# eightbyeight-teardrop.net
KiCad netlist of a schematic drawn in EAGLE
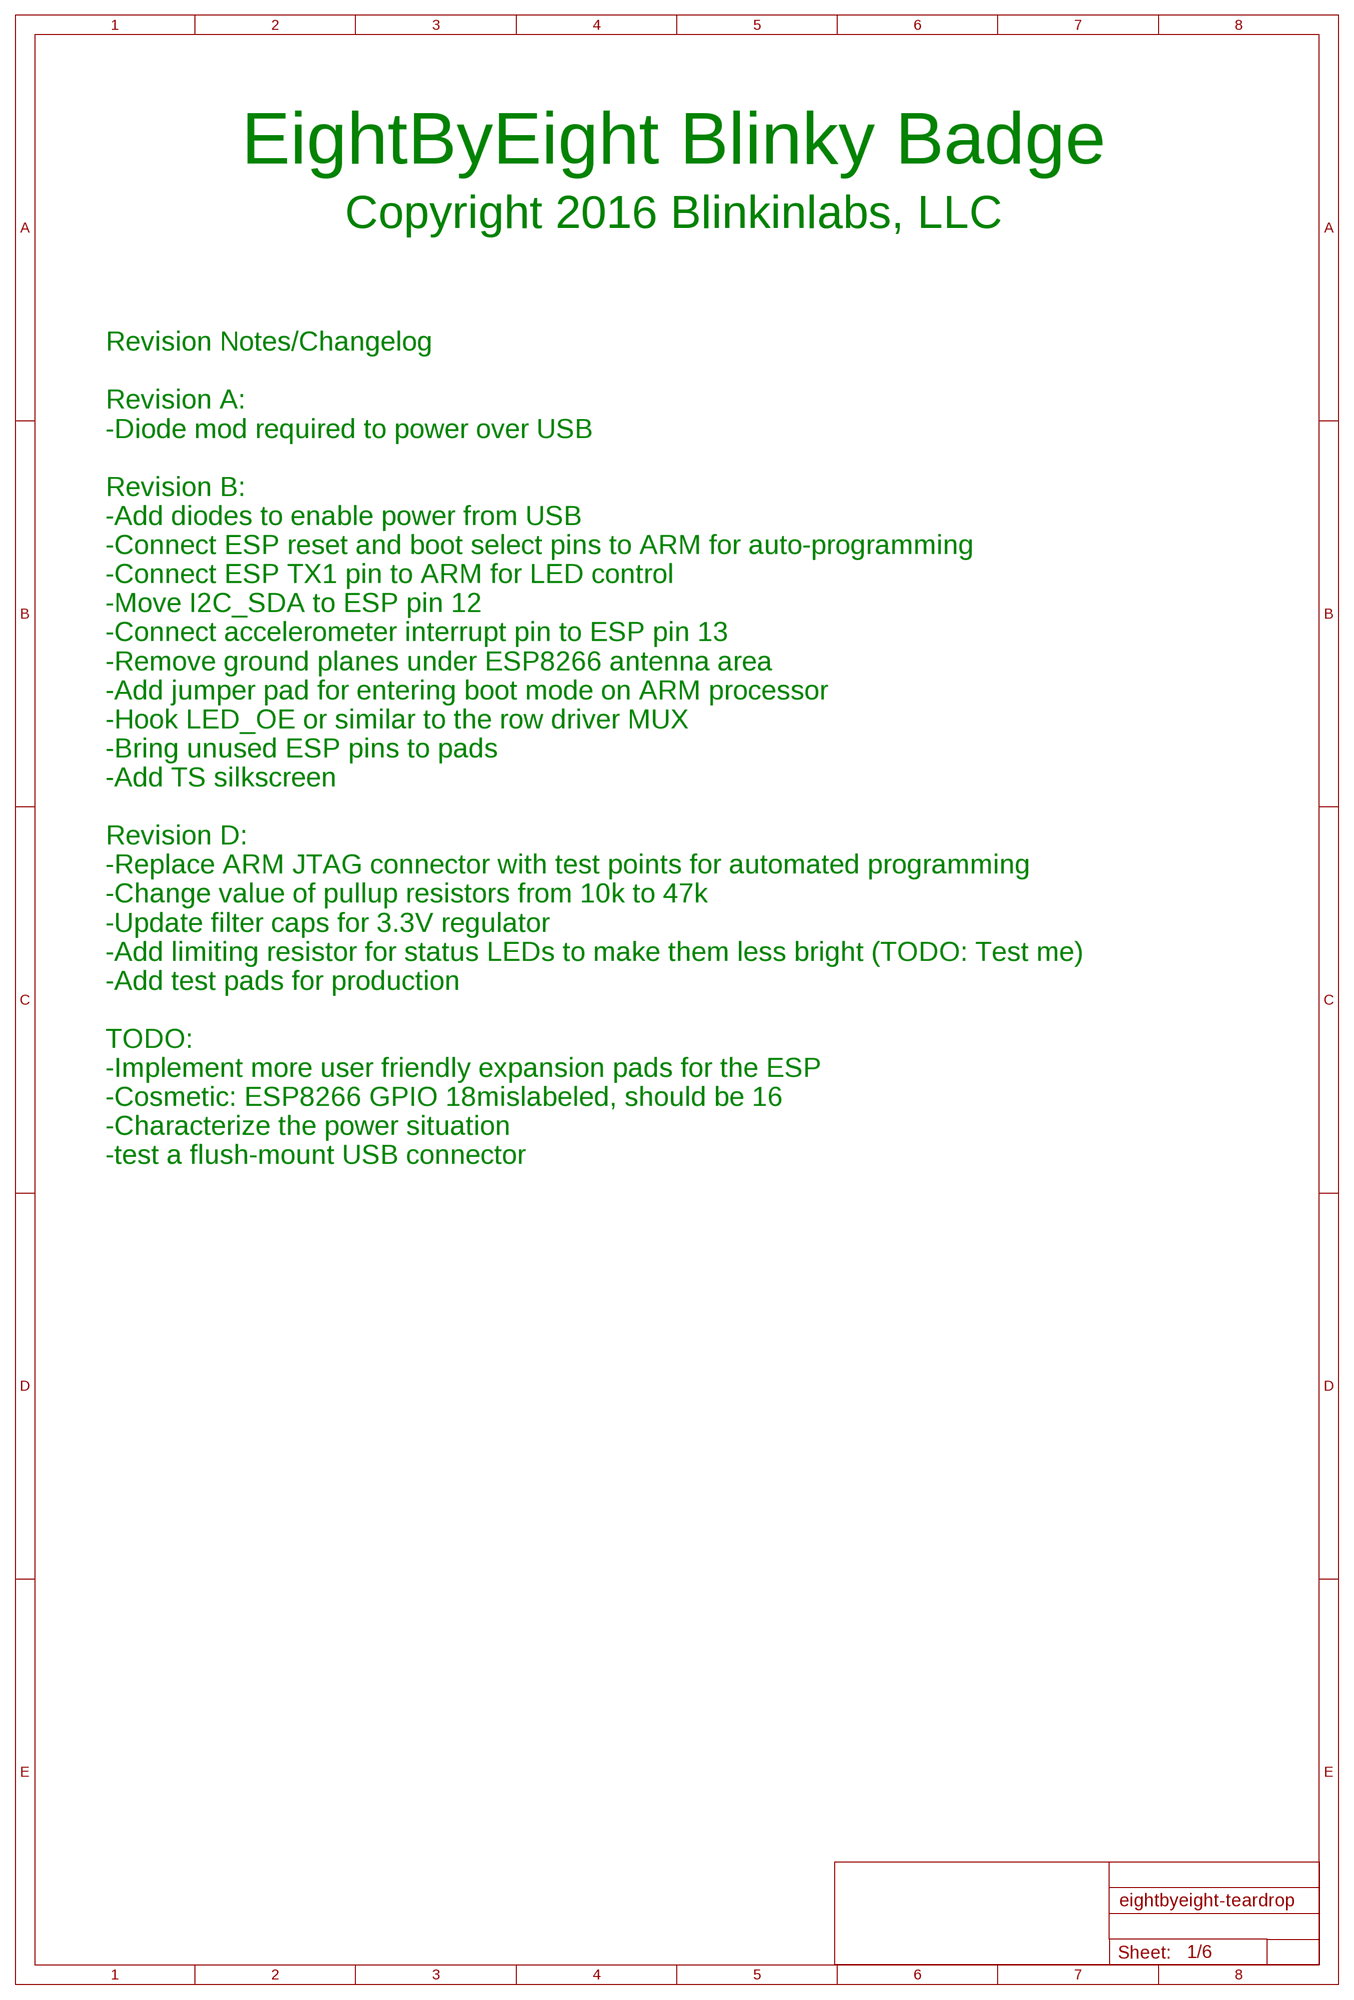
[diagram p0: schematic, sheet 1]
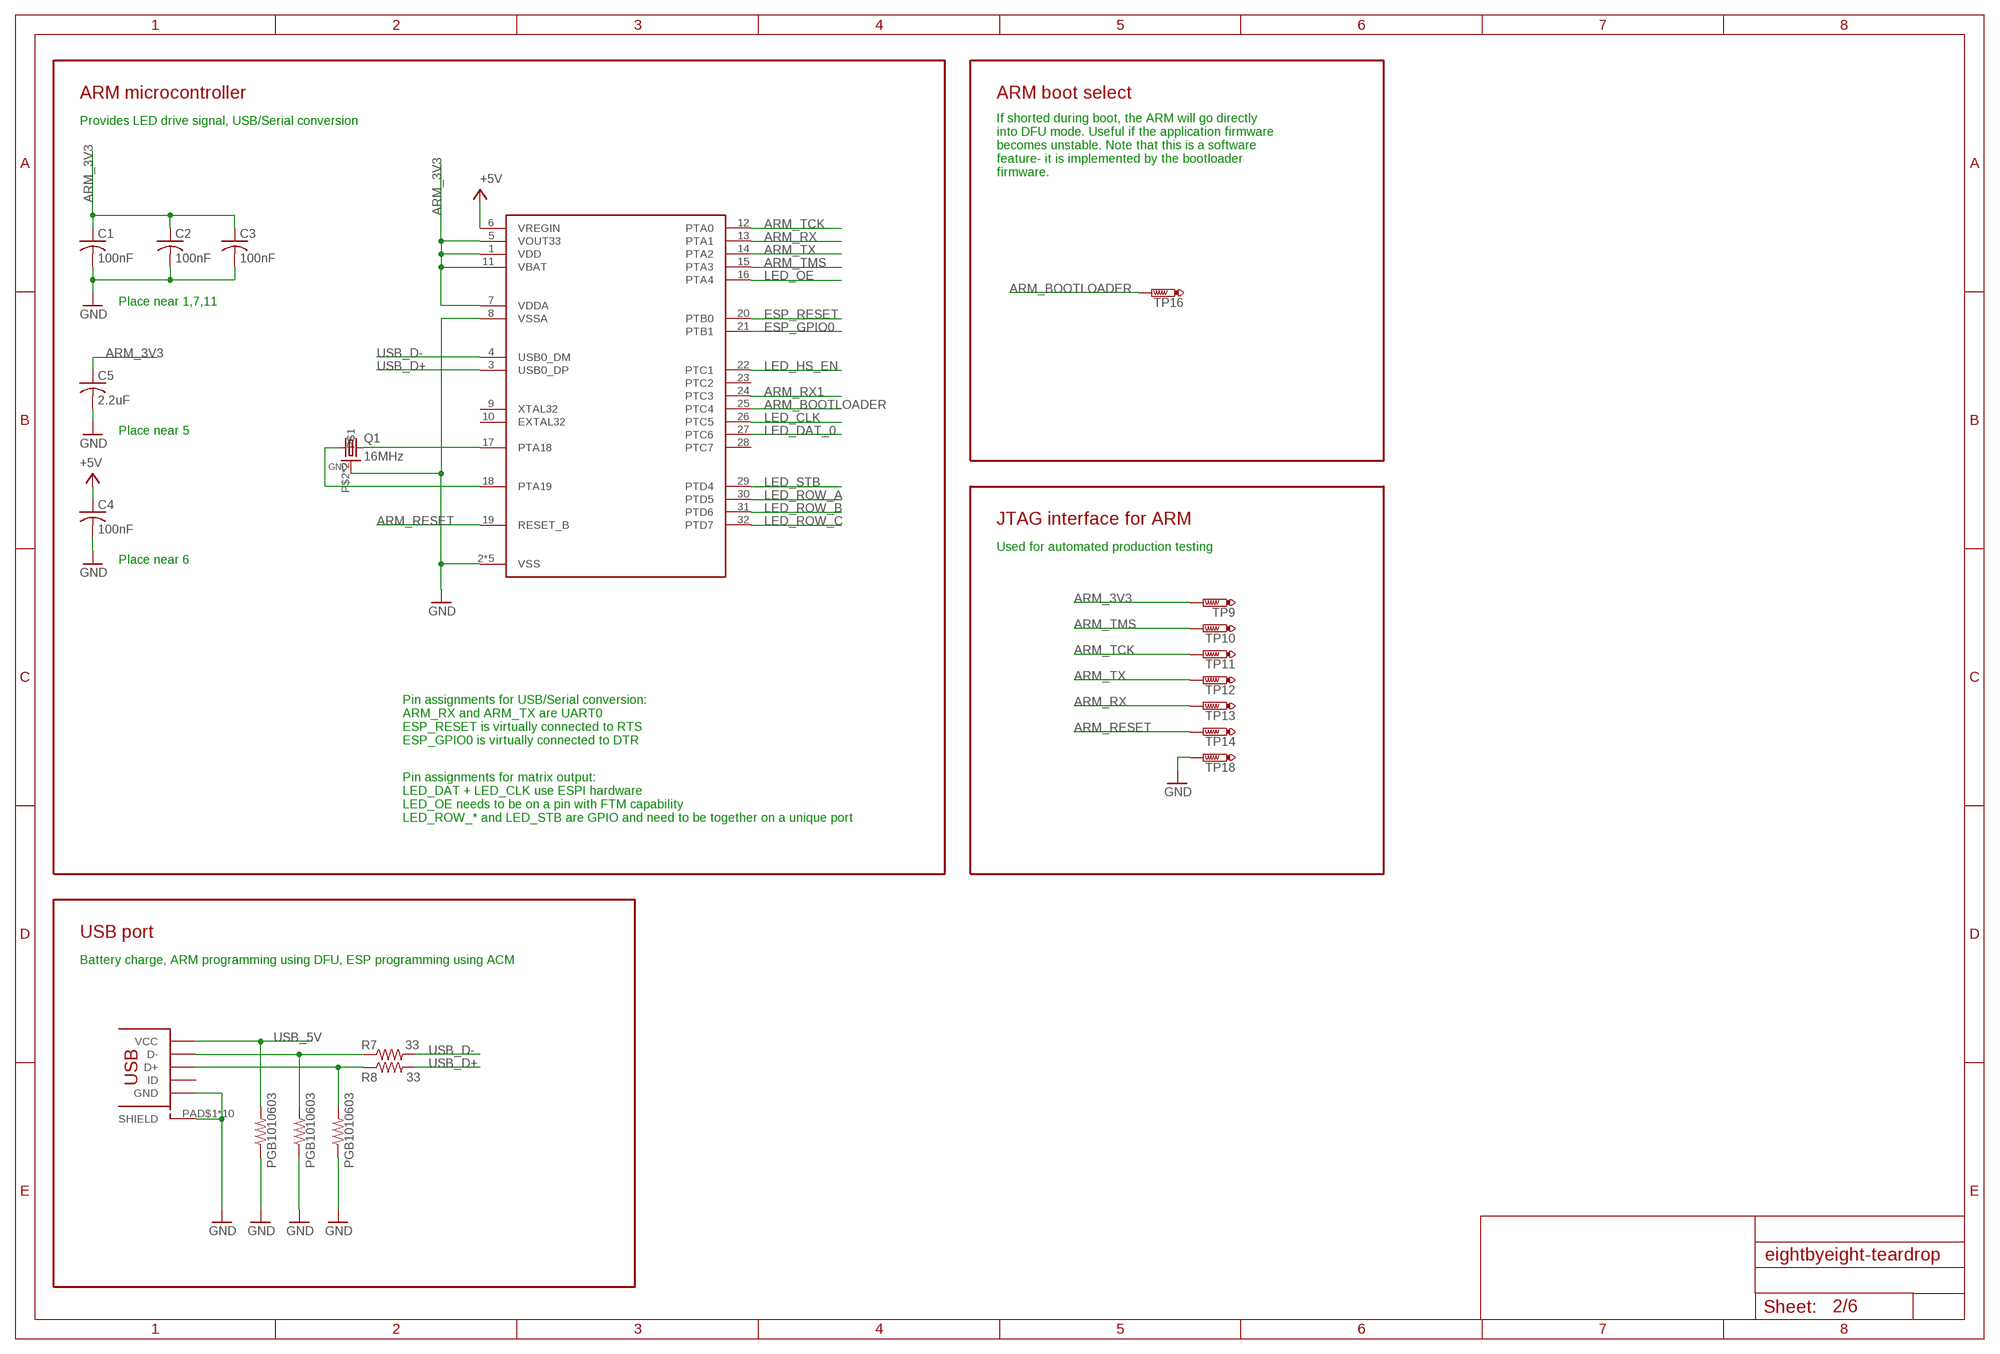
[diagram p1: schematic, sheet 2]
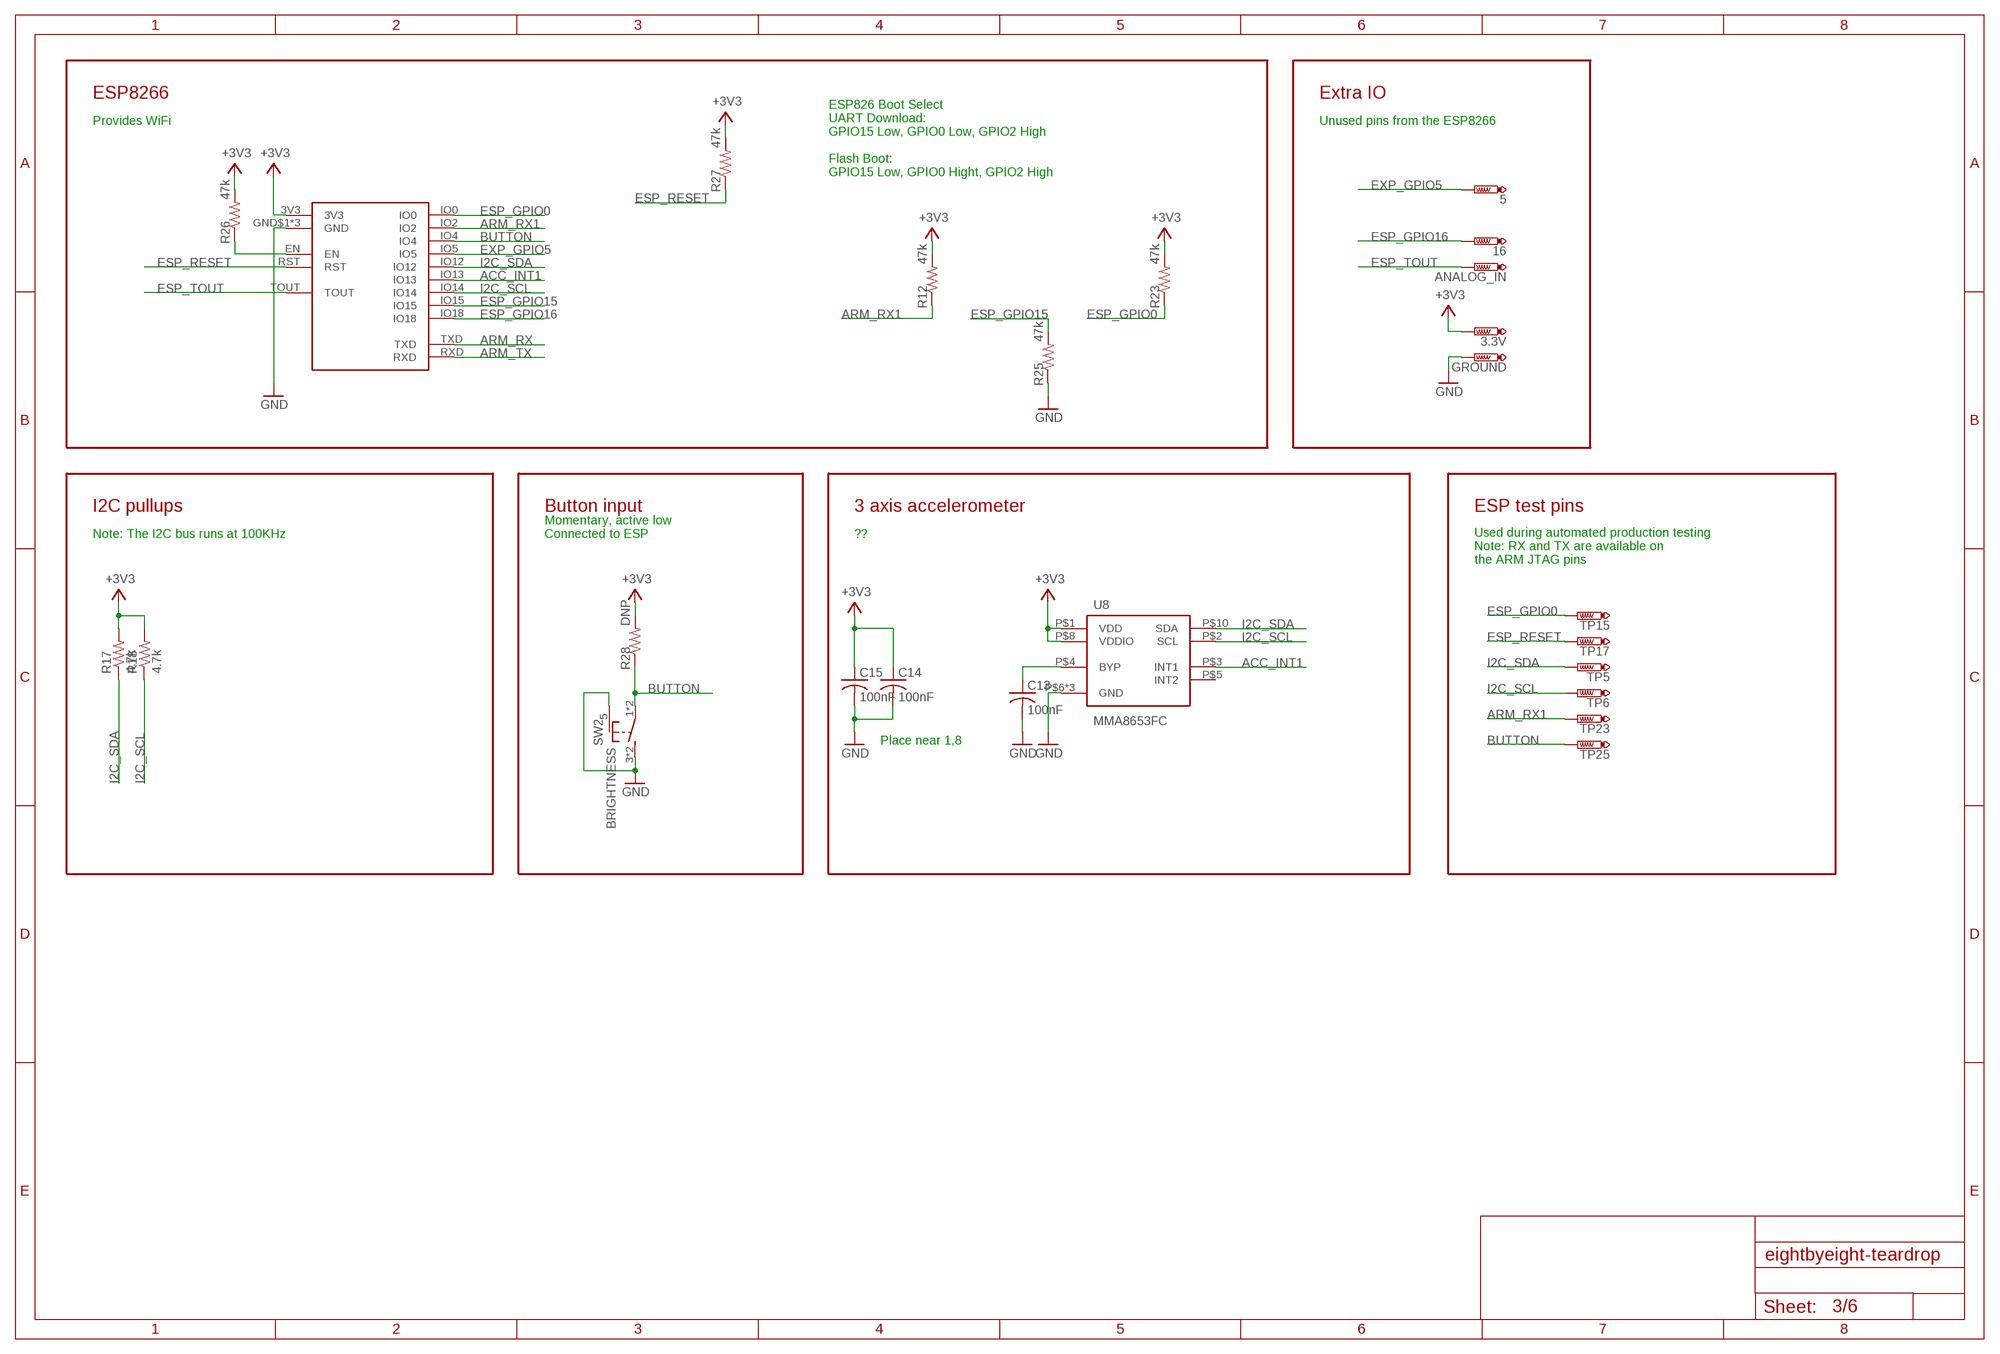
[diagram p2: schematic, sheet 3]
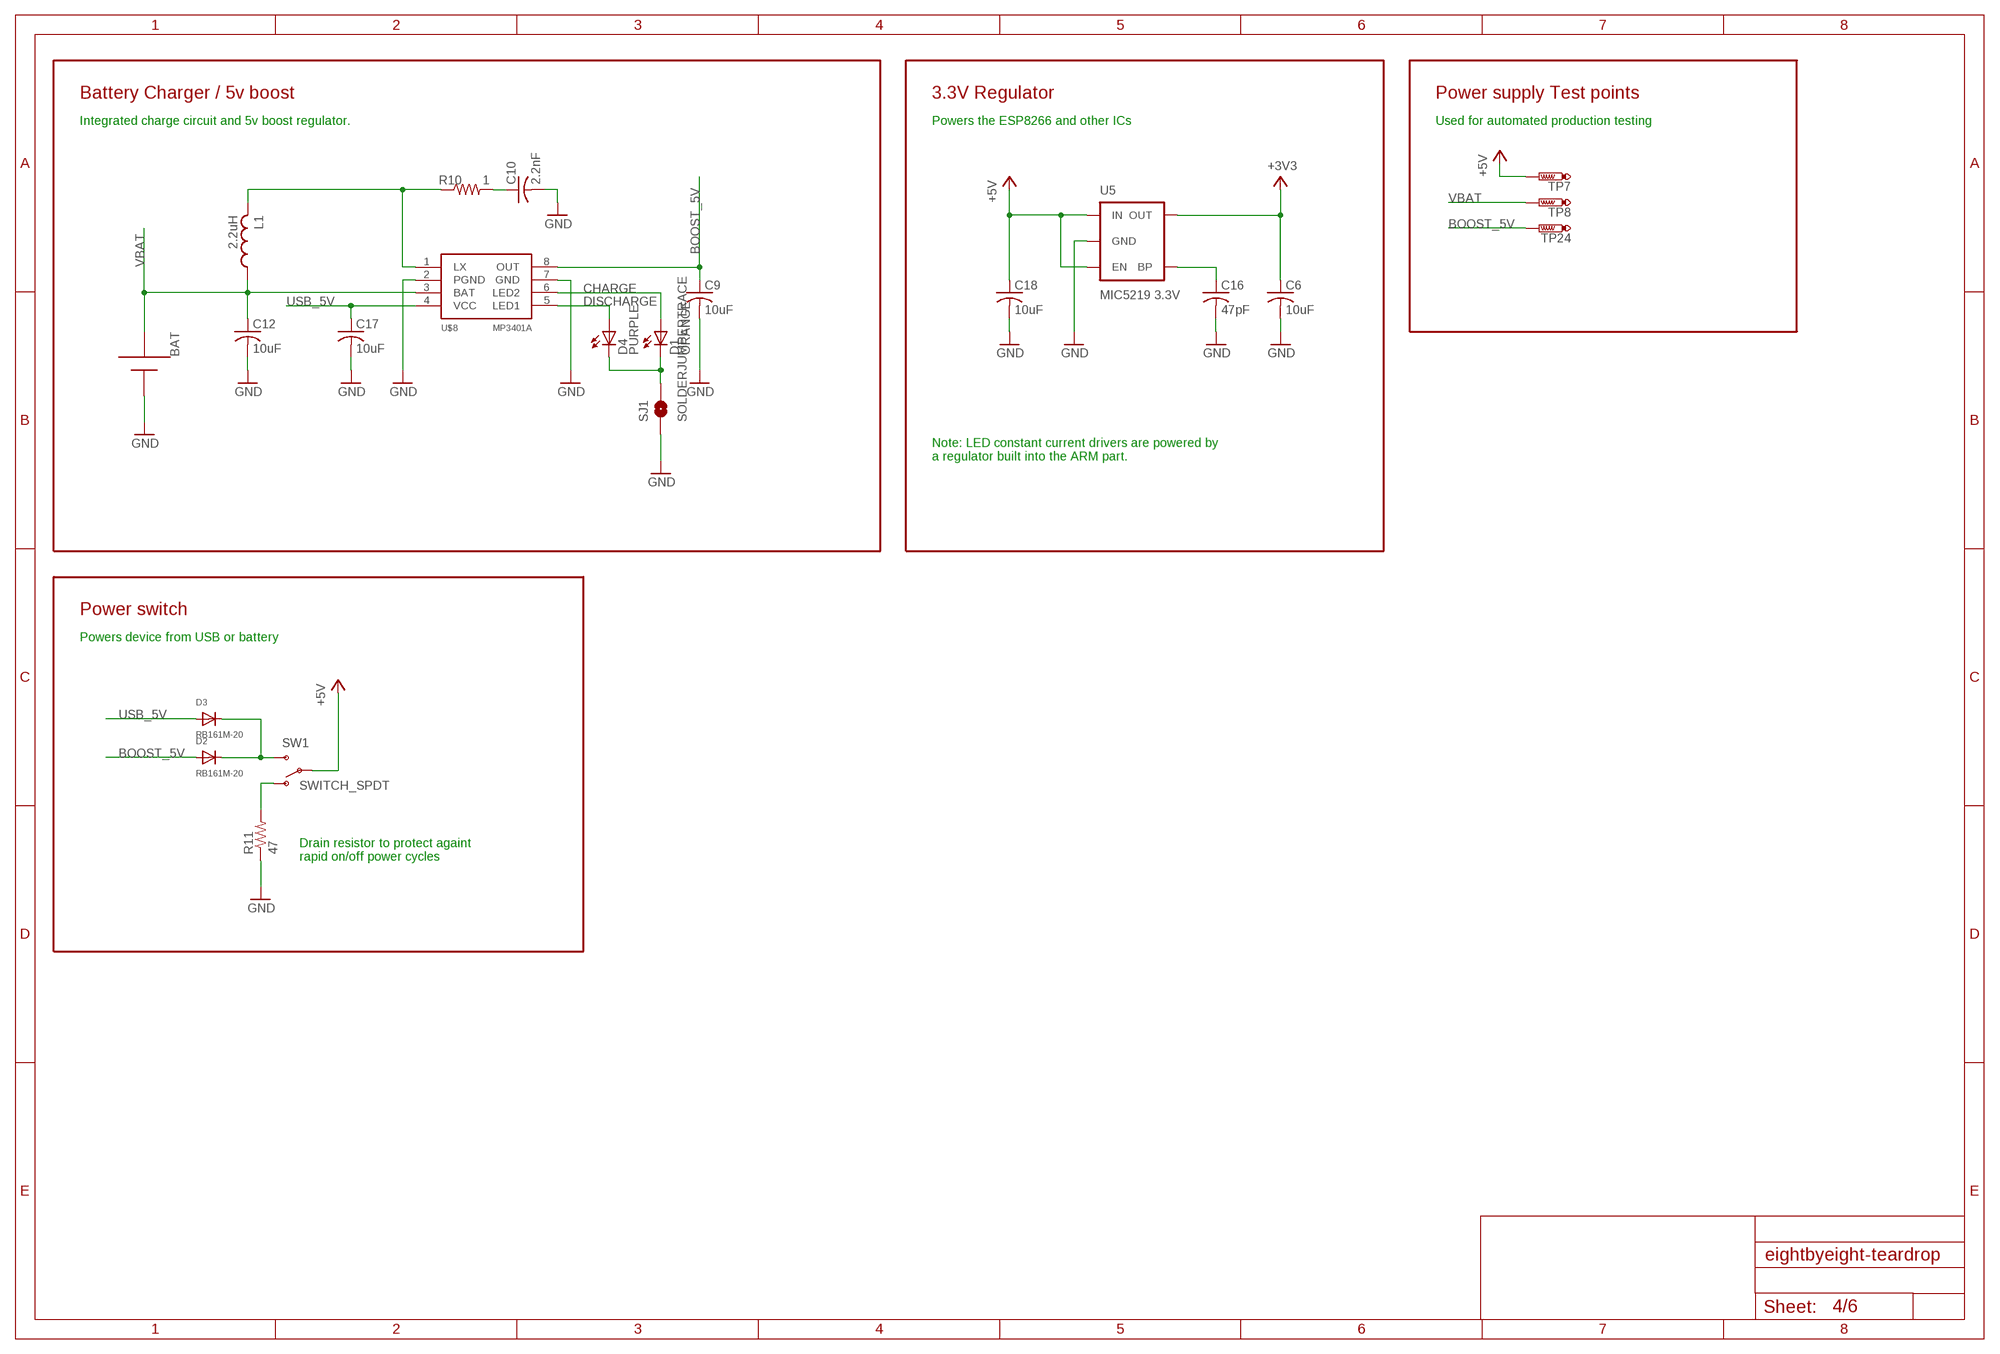
[diagram p3: schematic, sheet 4]
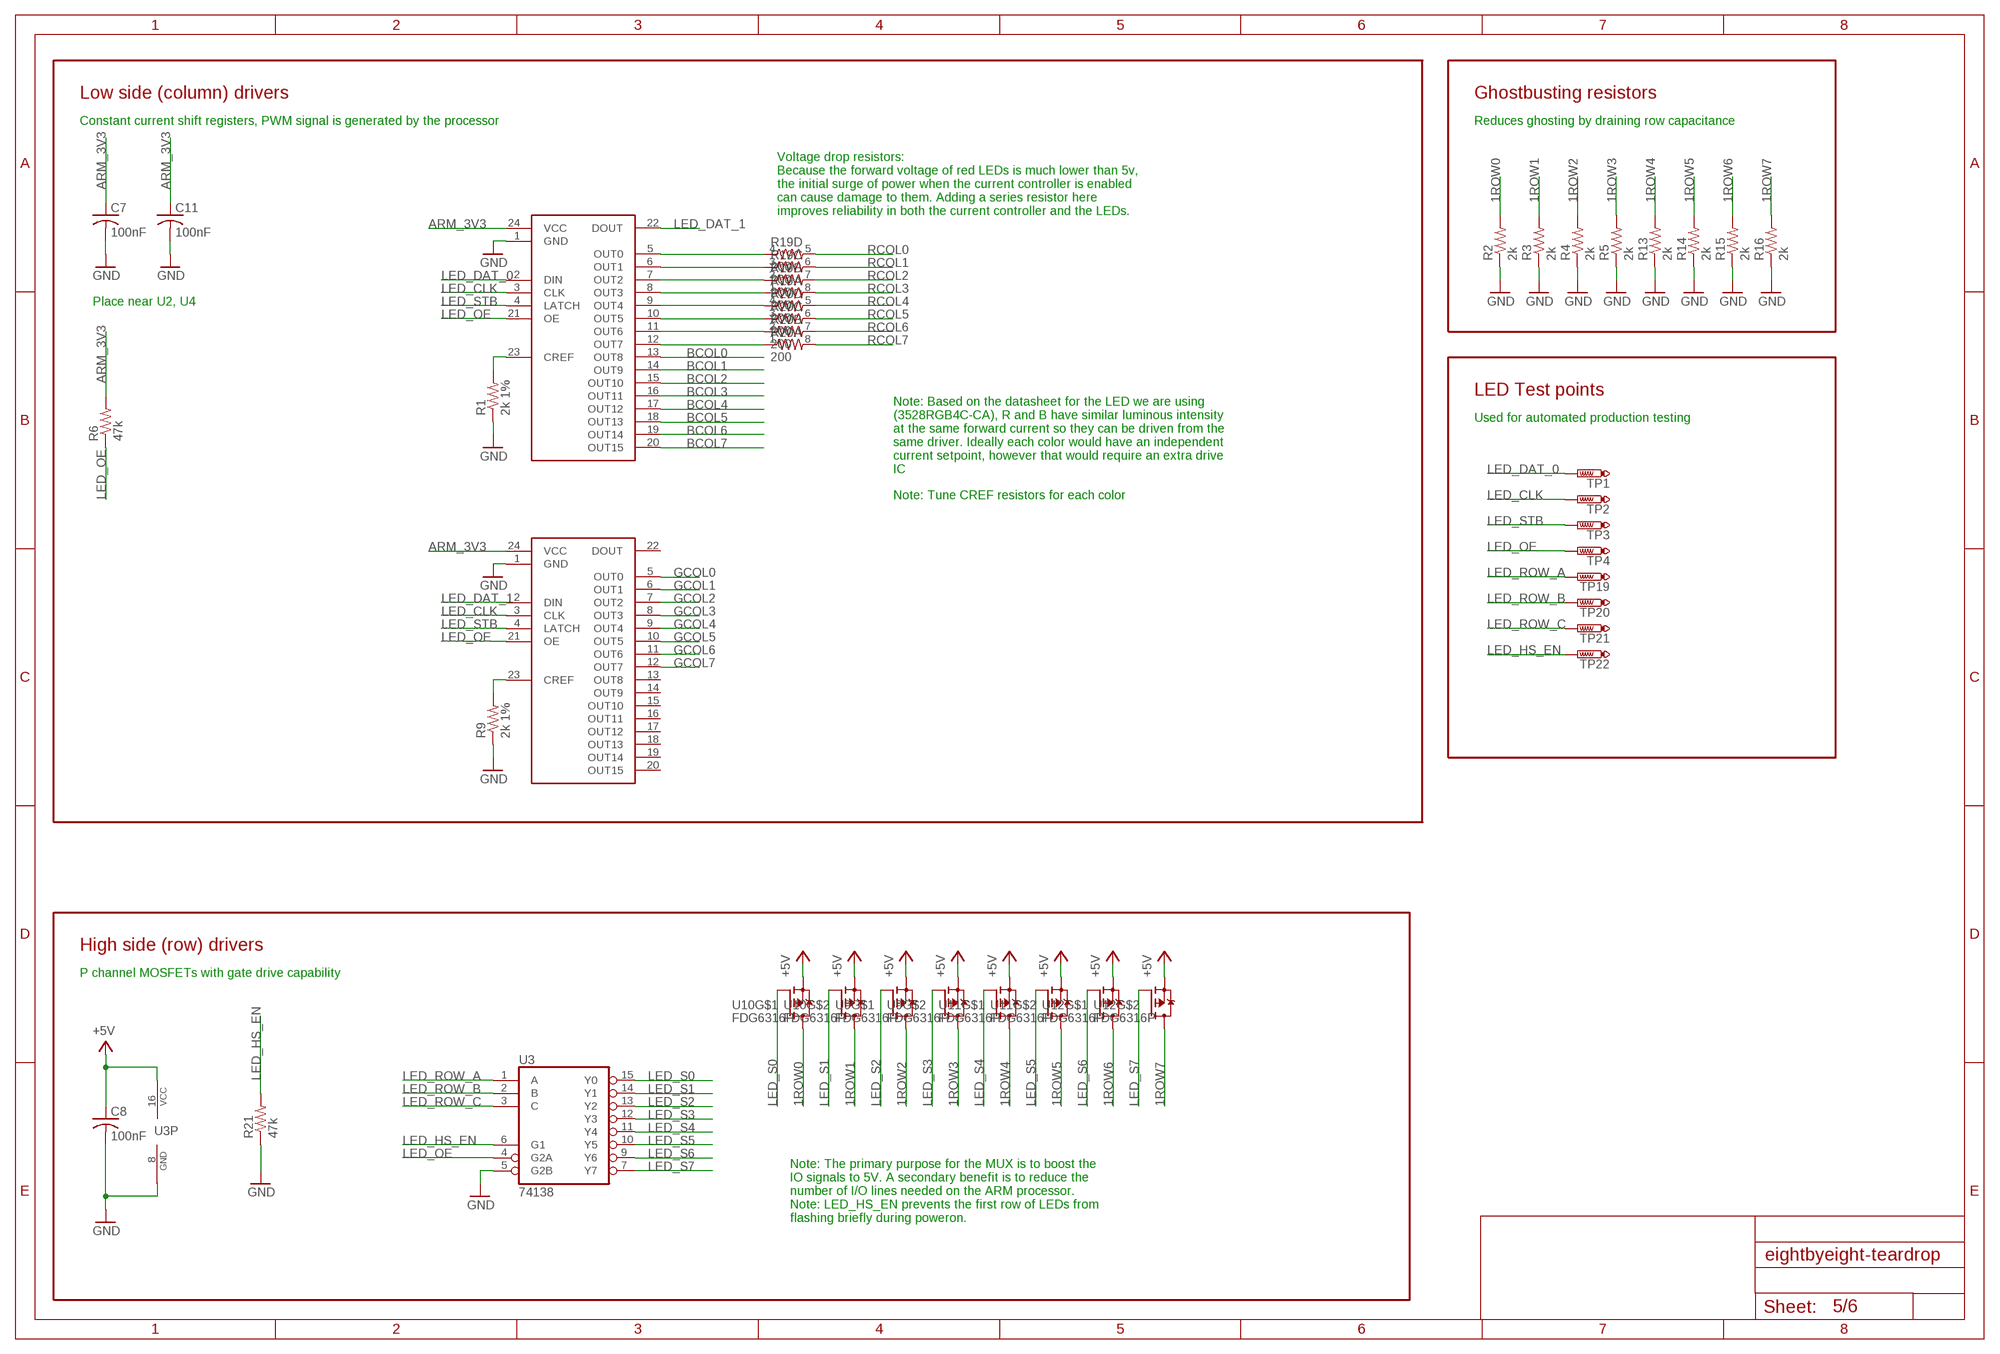
[diagram p4: schematic, sheet 5]
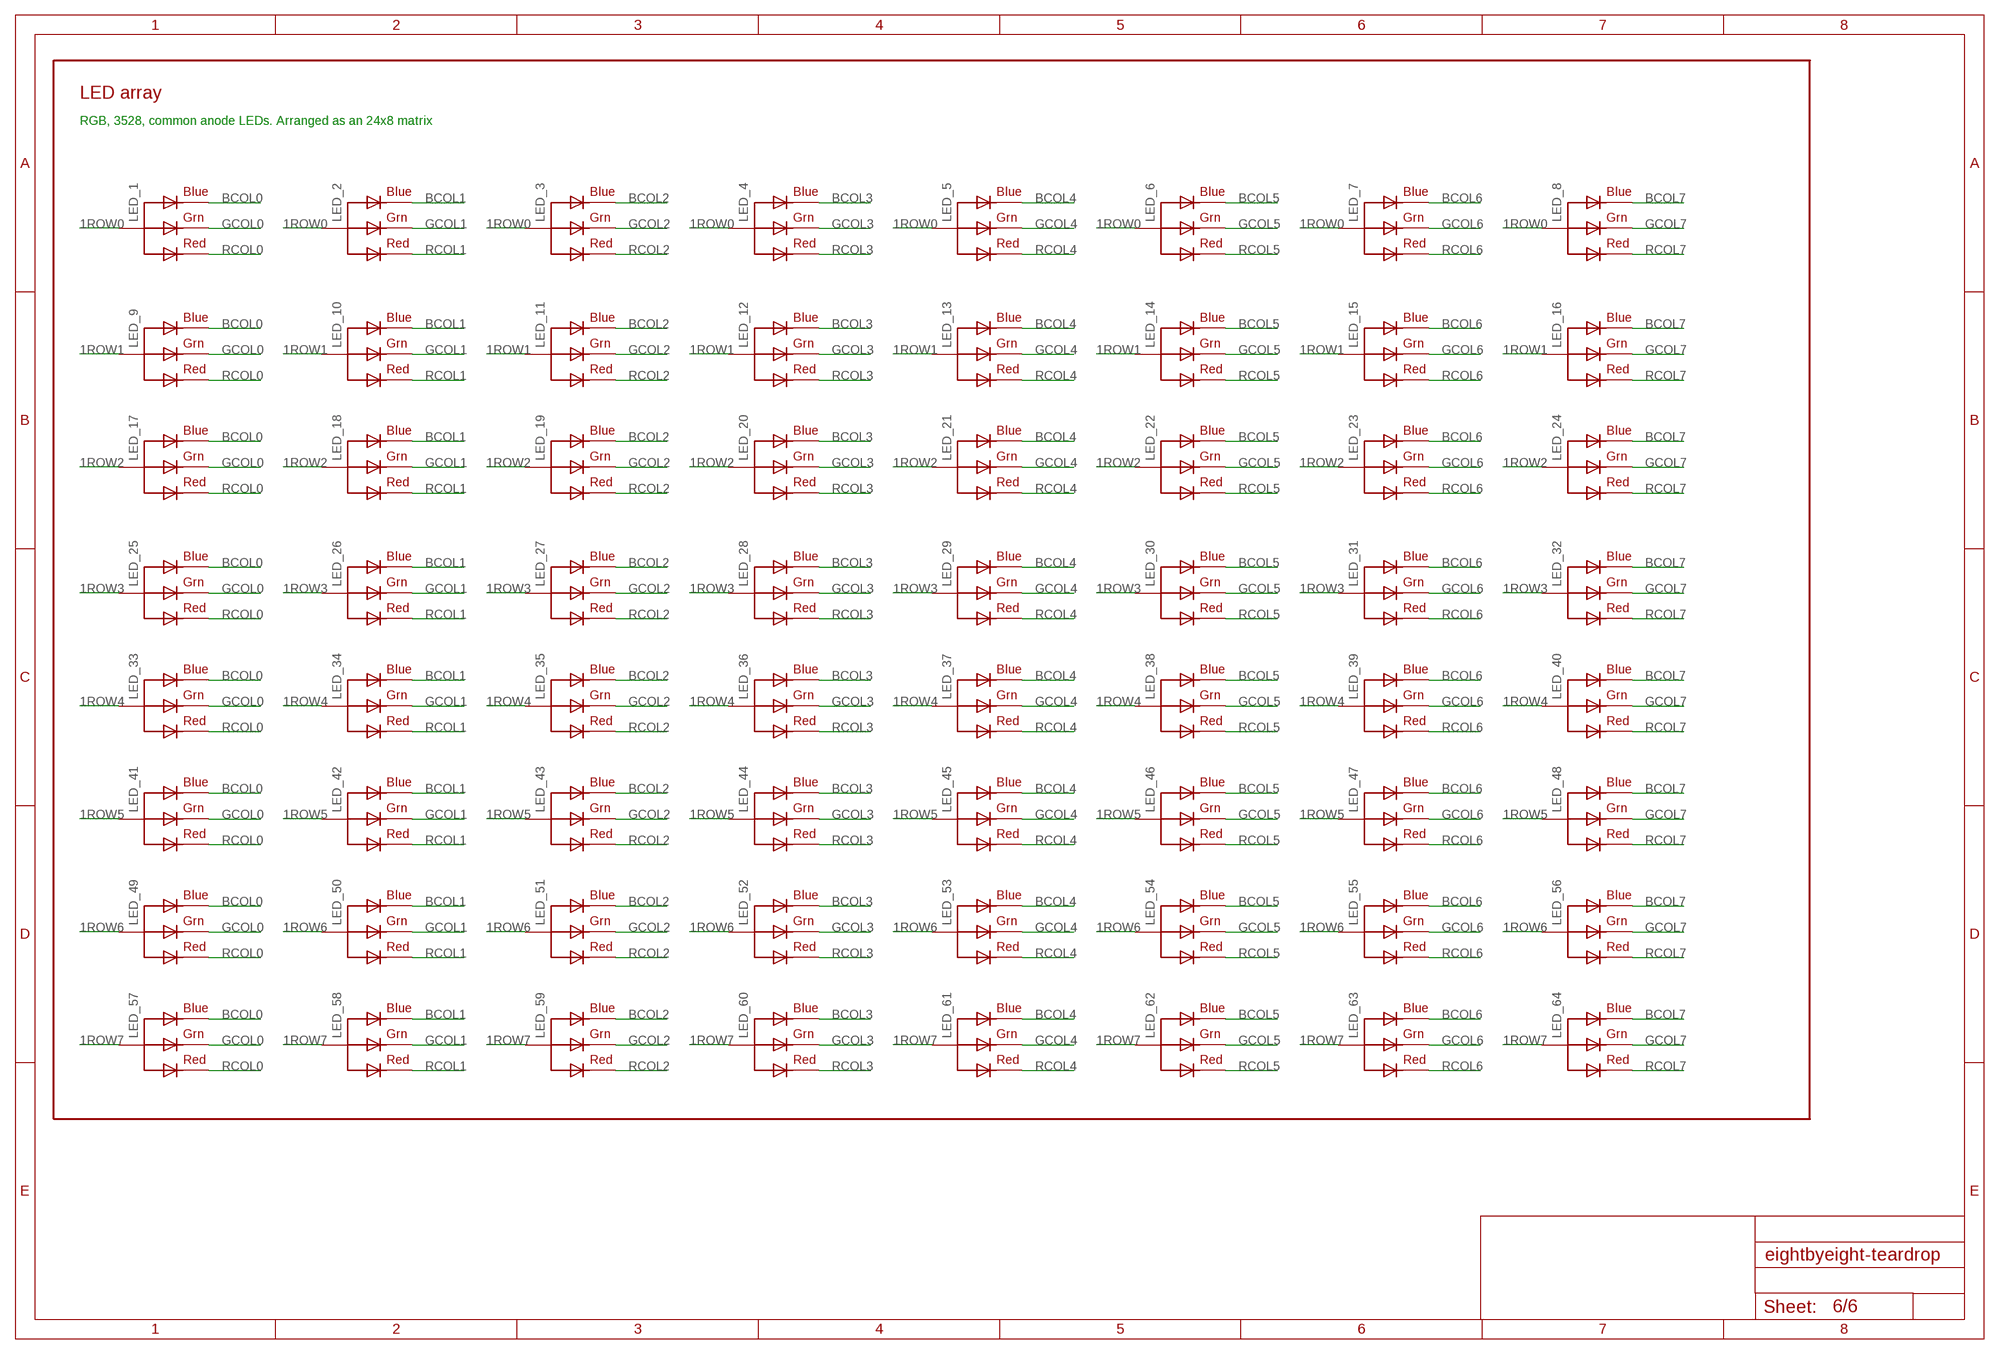
[diagram p5: schematic, sheet 6]

(export (version "E")
  (design (tool "Eeschema 10.0.6"))
  (components
    (comp (ref "C1")
      (value "100nF")
      (footprint "eagle-import:C0402")
      (libsource (lib "eagle-import") (part "C-USC0402"))
    )
    (comp (ref "C2")
      (value "100nF")
      (footprint "eagle-import:C0402")
      (libsource (lib "eagle-import") (part "C-USC0402"))
    )
    (comp (ref "C3")
      (value "100nF")
      (footprint "eagle-import:C0402")
      (libsource (lib "eagle-import") (part "C-USC0402"))
    )
    (comp (ref "C4")
      (value "100nF")
      (footprint "eagle-import:C0402")
      (libsource (lib "eagle-import") (part "C-USC0402"))
    )
    (comp (ref "C5")
      (value "2.2uF")
      (footprint "eagle-import:C0402")
      (libsource (lib "eagle-import") (part "C-USC0402"))
    )
    (comp (ref "CON1")
      (value "USB_MICROSMT+THRUHULE")
      (footprint "eagle-import:USB_MICRO_THRUHOLE")
      (libsource (lib "eagle-import") (part "USB_MICROSMT+THRUHULE"))
    )
    (comp (ref "Q1")
      (value "16MHz")
      (footprint "eagle-import:CRSYTAL_2520")
      (libsource (lib "eagle-import") (part "CRYSTAL_4PAD2520"))
    )
    (comp (ref "R7")
      (value "33")
      (footprint "eagle-import:R0402")
      (libsource (lib "eagle-import") (part "R-US_R0402"))
    )
    (comp (ref "R8")
      (value "33")
      (footprint "eagle-import:R0402")
      (libsource (lib "eagle-import") (part "R-US_R0402"))
    )
    (comp (ref "TP9")
      (value "PTR1B1,27")
      (footprint "eagle-import:B1,27")
      (libsource (lib "eagle-import") (part "PTR1B1,27"))
    )
    (comp (ref "TP10")
      (value "PTR1B1,27")
      (footprint "eagle-import:B1,27")
      (libsource (lib "eagle-import") (part "PTR1B1,27"))
    )
    (comp (ref "TP11")
      (value "PTR1B1,27")
      (footprint "eagle-import:B1,27")
      (libsource (lib "eagle-import") (part "PTR1B1,27"))
    )
    (comp (ref "TP12")
      (value "PTR1B1,27")
      (footprint "eagle-import:B1,27")
      (libsource (lib "eagle-import") (part "PTR1B1,27"))
    )
    (comp (ref "TP13")
      (value "PTR1B1,27")
      (footprint "eagle-import:B1,27")
      (libsource (lib "eagle-import") (part "PTR1B1,27"))
    )
    (comp (ref "TP14")
      (value "PTR1B1,27")
      (footprint "eagle-import:B1,27")
      (libsource (lib "eagle-import") (part "PTR1B1,27"))
    )
    (comp (ref "TP16")
      (value "PTR1B1,27")
      (footprint "eagle-import:B1,27")
      (libsource (lib "eagle-import") (part "PTR1B1,27"))
    )
    (comp (ref "TP18")
      (value "PTR1B1,27")
      (footprint "eagle-import:B1,27")
      (libsource (lib "eagle-import") (part "PTR1B1,27"))
    )
    (comp (ref "U1")
      (value "MK20DN64VFM5")
      (footprint "eagle-import:QFN32_5X5_LONGLEADS")
      (libsource (lib "eagle-import") (part "MK20D--VFM5"))
    )
    (comp (ref "Z1")
      (value "PGB1010603")
      (footprint "eagle-import:SPARKFUN-RESISTORS_0603-RES")
      (fields (field (name "MF") "Littelfuse") (field (name "MPN") "PGB1010603NRHF"))
      (libsource (lib "eagle-import") (part "SPARKFUN-RESISTORS_RESISTOR0603-RES"))
    )
    (comp (ref "Z2")
      (value "PGB1010603")
      (footprint "eagle-import:SPARKFUN-RESISTORS_0603-RES")
      (fields (field (name "MF") "Littelfuse") (field (name "MPN") "PGB1010603NRHF"))
      (libsource (lib "eagle-import") (part "SPARKFUN-RESISTORS_RESISTOR0603-RES"))
    )
    (comp (ref "Z3")
      (value "PGB1010603")
      (footprint "eagle-import:SPARKFUN-RESISTORS_0603-RES")
      (fields (field (name "MF") "Littelfuse") (field (name "MPN") "PGB1010603NRHF"))
      (libsource (lib "eagle-import") (part "SPARKFUN-RESISTORS_RESISTOR0603-RES"))
    )
    (comp (ref "LED_1")
      (value "LED_RGB_CA")
      (footprint "eagle-import:LED_3528")
      (libsource (lib "eagle-import") (part "LED_RGB_CA"))
    )
    (comp (ref "LED_2")
      (value "LED_RGB_CA")
      (footprint "eagle-import:LED_3528")
      (libsource (lib "eagle-import") (part "LED_RGB_CA"))
    )
    (comp (ref "LED_3")
      (value "LED_RGB_CA")
      (footprint "eagle-import:LED_3528")
      (libsource (lib "eagle-import") (part "LED_RGB_CA"))
    )
    (comp (ref "LED_4")
      (value "LED_RGB_CA")
      (footprint "eagle-import:LED_3528")
      (libsource (lib "eagle-import") (part "LED_RGB_CA"))
    )
    (comp (ref "LED_5")
      (value "LED_RGB_CA")
      (footprint "eagle-import:LED_3528")
      (libsource (lib "eagle-import") (part "LED_RGB_CA"))
    )
    (comp (ref "LED_6")
      (value "LED_RGB_CA")
      (footprint "eagle-import:LED_3528")
      (libsource (lib "eagle-import") (part "LED_RGB_CA"))
    )
    (comp (ref "LED_7")
      (value "LED_RGB_CA")
      (footprint "eagle-import:LED_3528")
      (libsource (lib "eagle-import") (part "LED_RGB_CA"))
    )
    (comp (ref "LED_8")
      (value "LED_RGB_CA")
      (footprint "eagle-import:LED_3528")
      (libsource (lib "eagle-import") (part "LED_RGB_CA"))
    )
    (comp (ref "LED_9")
      (value "LED_RGB_CA")
      (footprint "eagle-import:LED_3528")
      (libsource (lib "eagle-import") (part "LED_RGB_CA"))
    )
    (comp (ref "LED_10")
      (value "LED_RGB_CA")
      (footprint "eagle-import:LED_3528")
      (libsource (lib "eagle-import") (part "LED_RGB_CA"))
    )
    (comp (ref "LED_11")
      (value "LED_RGB_CA")
      (footprint "eagle-import:LED_3528")
      (libsource (lib "eagle-import") (part "LED_RGB_CA"))
    )
    (comp (ref "LED_12")
      (value "LED_RGB_CA")
      (footprint "eagle-import:LED_3528")
      (libsource (lib "eagle-import") (part "LED_RGB_CA"))
    )
    (comp (ref "LED_13")
      (value "LED_RGB_CA")
      (footprint "eagle-import:LED_3528")
      (libsource (lib "eagle-import") (part "LED_RGB_CA"))
    )
    (comp (ref "LED_14")
      (value "LED_RGB_CA")
      (footprint "eagle-import:LED_3528")
      (libsource (lib "eagle-import") (part "LED_RGB_CA"))
    )
    (comp (ref "LED_15")
      (value "LED_RGB_CA")
      (footprint "eagle-import:LED_3528")
      (libsource (lib "eagle-import") (part "LED_RGB_CA"))
    )
    (comp (ref "LED_16")
      (value "LED_RGB_CA")
      (footprint "eagle-import:LED_3528")
      (libsource (lib "eagle-import") (part "LED_RGB_CA"))
    )
    (comp (ref "LED_17")
      (value "LED_RGB_CA")
      (footprint "eagle-import:LED_3528")
      (libsource (lib "eagle-import") (part "LED_RGB_CA"))
    )
    (comp (ref "LED_18")
      (value "LED_RGB_CA")
      (footprint "eagle-import:LED_3528")
      (libsource (lib "eagle-import") (part "LED_RGB_CA"))
    )
    (comp (ref "LED_19")
      (value "LED_RGB_CA")
      (footprint "eagle-import:LED_3528")
      (libsource (lib "eagle-import") (part "LED_RGB_CA"))
    )
    (comp (ref "LED_20")
      (value "LED_RGB_CA")
      (footprint "eagle-import:LED_3528")
      (libsource (lib "eagle-import") (part "LED_RGB_CA"))
    )
    (comp (ref "LED_21")
      (value "LED_RGB_CA")
      (footprint "eagle-import:LED_3528")
      (libsource (lib "eagle-import") (part "LED_RGB_CA"))
    )
    (comp (ref "LED_22")
      (value "LED_RGB_CA")
      (footprint "eagle-import:LED_3528")
      (libsource (lib "eagle-import") (part "LED_RGB_CA"))
    )
    (comp (ref "LED_23")
      (value "LED_RGB_CA")
      (footprint "eagle-import:LED_3528")
      (libsource (lib "eagle-import") (part "LED_RGB_CA"))
    )
    (comp (ref "LED_24")
      (value "LED_RGB_CA")
      (footprint "eagle-import:LED_3528")
      (libsource (lib "eagle-import") (part "LED_RGB_CA"))
    )
    (comp (ref "LED_25")
      (value "LED_RGB_CA")
      (footprint "eagle-import:LED_3528")
      (libsource (lib "eagle-import") (part "LED_RGB_CA"))
    )
    (comp (ref "LED_26")
      (value "LED_RGB_CA")
      (footprint "eagle-import:LED_3528")
      (libsource (lib "eagle-import") (part "LED_RGB_CA"))
    )
    (comp (ref "LED_27")
      (value "LED_RGB_CA")
      (footprint "eagle-import:LED_3528")
      (libsource (lib "eagle-import") (part "LED_RGB_CA"))
    )
    (comp (ref "LED_28")
      (value "LED_RGB_CA")
      (footprint "eagle-import:LED_3528")
      (libsource (lib "eagle-import") (part "LED_RGB_CA"))
    )
    (comp (ref "LED_29")
      (value "LED_RGB_CA")
      (footprint "eagle-import:LED_3528")
      (libsource (lib "eagle-import") (part "LED_RGB_CA"))
    )
    (comp (ref "LED_30")
      (value "LED_RGB_CA")
      (footprint "eagle-import:LED_3528")
      (libsource (lib "eagle-import") (part "LED_RGB_CA"))
    )
    (comp (ref "LED_31")
      (value "LED_RGB_CA")
      (footprint "eagle-import:LED_3528")
      (libsource (lib "eagle-import") (part "LED_RGB_CA"))
    )
    (comp (ref "LED_32")
      (value "LED_RGB_CA")
      (footprint "eagle-import:LED_3528")
      (libsource (lib "eagle-import") (part "LED_RGB_CA"))
    )
    (comp (ref "LED_33")
      (value "LED_RGB_CA")
      (footprint "eagle-import:LED_3528")
      (libsource (lib "eagle-import") (part "LED_RGB_CA"))
    )
    (comp (ref "LED_34")
      (value "LED_RGB_CA")
      (footprint "eagle-import:LED_3528")
      (libsource (lib "eagle-import") (part "LED_RGB_CA"))
    )
    (comp (ref "LED_35")
      (value "LED_RGB_CA")
      (footprint "eagle-import:LED_3528")
      (libsource (lib "eagle-import") (part "LED_RGB_CA"))
    )
    (comp (ref "LED_36")
      (value "LED_RGB_CA")
      (footprint "eagle-import:LED_3528")
      (libsource (lib "eagle-import") (part "LED_RGB_CA"))
    )
    (comp (ref "LED_37")
      (value "LED_RGB_CA")
      (footprint "eagle-import:LED_3528")
      (libsource (lib "eagle-import") (part "LED_RGB_CA"))
    )
    (comp (ref "LED_38")
      (value "LED_RGB_CA")
      (footprint "eagle-import:LED_3528")
      (libsource (lib "eagle-import") (part "LED_RGB_CA"))
    )
    (comp (ref "LED_39")
      (value "LED_RGB_CA")
      (footprint "eagle-import:LED_3528")
      (libsource (lib "eagle-import") (part "LED_RGB_CA"))
    )
    (comp (ref "LED_40")
      (value "LED_RGB_CA")
      (footprint "eagle-import:LED_3528")
      (libsource (lib "eagle-import") (part "LED_RGB_CA"))
    )
    (comp (ref "LED_41")
      (value "LED_RGB_CA")
      (footprint "eagle-import:LED_3528")
      (libsource (lib "eagle-import") (part "LED_RGB_CA"))
    )
    (comp (ref "LED_42")
      (value "LED_RGB_CA")
      (footprint "eagle-import:LED_3528")
      (libsource (lib "eagle-import") (part "LED_RGB_CA"))
    )
    (comp (ref "LED_43")
      (value "LED_RGB_CA")
      (footprint "eagle-import:LED_3528")
      (libsource (lib "eagle-import") (part "LED_RGB_CA"))
    )
    (comp (ref "LED_44")
      (value "LED_RGB_CA")
      (footprint "eagle-import:LED_3528")
      (libsource (lib "eagle-import") (part "LED_RGB_CA"))
    )
    (comp (ref "LED_45")
      (value "LED_RGB_CA")
      (footprint "eagle-import:LED_3528")
      (libsource (lib "eagle-import") (part "LED_RGB_CA"))
    )
    (comp (ref "LED_46")
      (value "LED_RGB_CA")
      (footprint "eagle-import:LED_3528")
      (libsource (lib "eagle-import") (part "LED_RGB_CA"))
    )
    (comp (ref "LED_47")
      (value "LED_RGB_CA")
      (footprint "eagle-import:LED_3528")
      (libsource (lib "eagle-import") (part "LED_RGB_CA"))
    )
    (comp (ref "LED_48")
      (value "LED_RGB_CA")
      (footprint "eagle-import:LED_3528")
      (libsource (lib "eagle-import") (part "LED_RGB_CA"))
    )
    (comp (ref "LED_49")
      (value "LED_RGB_CA")
      (footprint "eagle-import:LED_3528")
      (libsource (lib "eagle-import") (part "LED_RGB_CA"))
    )
    (comp (ref "LED_50")
      (value "LED_RGB_CA")
      (footprint "eagle-import:LED_3528")
      (libsource (lib "eagle-import") (part "LED_RGB_CA"))
    )
    (comp (ref "LED_51")
      (value "LED_RGB_CA")
      (footprint "eagle-import:LED_3528")
      (libsource (lib "eagle-import") (part "LED_RGB_CA"))
    )
    (comp (ref "LED_52")
      (value "LED_RGB_CA")
      (footprint "eagle-import:LED_3528")
      (libsource (lib "eagle-import") (part "LED_RGB_CA"))
    )
    (comp (ref "LED_53")
      (value "LED_RGB_CA")
      (footprint "eagle-import:LED_3528")
      (libsource (lib "eagle-import") (part "LED_RGB_CA"))
    )
    (comp (ref "LED_54")
      (value "LED_RGB_CA")
      (footprint "eagle-import:LED_3528")
      (libsource (lib "eagle-import") (part "LED_RGB_CA"))
    )
    (comp (ref "LED_55")
      (value "LED_RGB_CA")
      (footprint "eagle-import:LED_3528")
      (libsource (lib "eagle-import") (part "LED_RGB_CA"))
    )
    (comp (ref "LED_56")
      (value "LED_RGB_CA")
      (footprint "eagle-import:LED_3528")
      (libsource (lib "eagle-import") (part "LED_RGB_CA"))
    )
    (comp (ref "LED_57")
      (value "LED_RGB_CA")
      (footprint "eagle-import:LED_3528")
      (libsource (lib "eagle-import") (part "LED_RGB_CA"))
    )
    (comp (ref "LED_58")
      (value "LED_RGB_CA")
      (footprint "eagle-import:LED_3528")
      (libsource (lib "eagle-import") (part "LED_RGB_CA"))
    )
    (comp (ref "LED_59")
      (value "LED_RGB_CA")
      (footprint "eagle-import:LED_3528")
      (libsource (lib "eagle-import") (part "LED_RGB_CA"))
    )
    (comp (ref "LED_60")
      (value "LED_RGB_CA")
      (footprint "eagle-import:LED_3528")
      (libsource (lib "eagle-import") (part "LED_RGB_CA"))
    )
    (comp (ref "LED_61")
      (value "LED_RGB_CA")
      (footprint "eagle-import:LED_3528")
      (libsource (lib "eagle-import") (part "LED_RGB_CA"))
    )
    (comp (ref "LED_62")
      (value "LED_RGB_CA")
      (footprint "eagle-import:LED_3528")
      (libsource (lib "eagle-import") (part "LED_RGB_CA"))
    )
    (comp (ref "LED_63")
      (value "LED_RGB_CA")
      (footprint "eagle-import:LED_3528")
      (libsource (lib "eagle-import") (part "LED_RGB_CA"))
    )
    (comp (ref "LED_64")
      (value "LED_RGB_CA")
      (footprint "eagle-import:LED_3528")
      (libsource (lib "eagle-import") (part "LED_RGB_CA"))
    )
    (comp (ref "C7")
      (value "100nF")
      (footprint "eagle-import:C0402")
      (libsource (lib "eagle-import") (part "C-USC0402"))
    )
    (comp (ref "C8")
      (value "100nF")
      (footprint "eagle-import:C0402")
      (libsource (lib "eagle-import") (part "C-USC0402"))
    )
    (comp (ref "C11")
      (value "100nF")
      (footprint "eagle-import:C0402")
      (libsource (lib "eagle-import") (part "C-USC0402"))
    )
    (comp (ref "R1")
      (value "2k 1%")
      (footprint "eagle-import:R0402")
      (libsource (lib "eagle-import") (part "R-US_R0402"))
    )
    (comp (ref "R2")
      (value "2k")
      (footprint "eagle-import:R0402")
      (libsource (lib "eagle-import") (part "R-US_R0402"))
    )
    (comp (ref "R3")
      (value "2k")
      (footprint "eagle-import:R0402")
      (libsource (lib "eagle-import") (part "R-US_R0402"))
    )
    (comp (ref "R4")
      (value "2k")
      (footprint "eagle-import:R0402")
      (libsource (lib "eagle-import") (part "R-US_R0402"))
    )
    (comp (ref "R5")
      (value "2k")
      (footprint "eagle-import:R0402")
      (libsource (lib "eagle-import") (part "R-US_R0402"))
    )
    (comp (ref "R6")
      (value "47k")
      (footprint "eagle-import:R0402")
      (libsource (lib "eagle-import") (part "R-US_R0402"))
    )
    (comp (ref "R9")
      (value "2k 1%")
      (footprint "eagle-import:R0402")
      (libsource (lib "eagle-import") (part "R-US_R0402"))
    )
    (comp (ref "R13")
      (value "2k")
      (footprint "eagle-import:R0402")
      (libsource (lib "eagle-import") (part "R-US_R0402"))
    )
    (comp (ref "R14")
      (value "2k")
      (footprint "eagle-import:R0402")
      (libsource (lib "eagle-import") (part "R-US_R0402"))
    )
    (comp (ref "R15")
      (value "2k")
      (footprint "eagle-import:R0402")
      (libsource (lib "eagle-import") (part "R-US_R0402"))
    )
    (comp (ref "R16")
      (value "2k")
      (footprint "eagle-import:R0402")
      (libsource (lib "eagle-import") (part "R-US_R0402"))
    )
    (comp (ref "R19")
      (value "200")
      (footprint "eagle-import:0603-ARV")
      (libsource (lib "eagle-import") (part "RESISTOR-ARRAY0603-ARV"))
    )
    (comp (ref "R20")
      (value "200")
      (footprint "eagle-import:0603-ARV")
      (libsource (lib "eagle-import") (part "RESISTOR-ARRAY0603-ARV"))
    )
    (comp (ref "R21")
      (value "47k")
      (footprint "eagle-import:R0402")
      (libsource (lib "eagle-import") (part "R-US_R0402"))
    )
    (comp (ref "TP1")
      (value "PTR1B1,27")
      (footprint "eagle-import:B1,27")
      (libsource (lib "eagle-import") (part "PTR1B1,27"))
    )
    (comp (ref "TP2")
      (value "PTR1B1,27")
      (footprint "eagle-import:B1,27")
      (libsource (lib "eagle-import") (part "PTR1B1,27"))
    )
    (comp (ref "TP3")
      (value "PTR1B1,27")
      (footprint "eagle-import:B1,27")
      (libsource (lib "eagle-import") (part "PTR1B1,27"))
    )
    (comp (ref "TP4")
      (value "PTR1B1,27")
      (footprint "eagle-import:B1,27")
      (libsource (lib "eagle-import") (part "PTR1B1,27"))
    )
    (comp (ref "TP19")
      (value "PTR1B1,27")
      (footprint "eagle-import:B1,27")
      (libsource (lib "eagle-import") (part "PTR1B1,27"))
    )
    (comp (ref "TP20")
      (value "PTR1B1,27")
      (footprint "eagle-import:B1,27")
      (libsource (lib "eagle-import") (part "PTR1B1,27"))
    )
    (comp (ref "TP21")
      (value "PTR1B1,27")
      (footprint "eagle-import:B1,27")
      (libsource (lib "eagle-import") (part "PTR1B1,27"))
    )
    (comp (ref "TP22")
      (value "PTR1B1,27")
      (footprint "eagle-import:B1,27")
      (libsource (lib "eagle-import") (part "PTR1B1,27"))
    )
    (comp (ref "U2")
      (value "ICN2026")
      (footprint "eagle-import:SSOP24-150")
      (libsource (lib "eagle-import") (part "ICN2026"))
    )
    (comp (ref "U3")
      (value "74138")
      (footprint "eagle-import:TSSOP16")
      (libsource (lib "eagle-import") (part "74138"))
    )
    (comp (ref "U4")
      (value "ICN2026")
      (footprint "eagle-import:SSOP24-150")
      (libsource (lib "eagle-import") (part "ICN2026"))
    )
    (comp (ref "U9")
      (value "FDG6316P")
      (footprint "eagle-import:SC70-6L")
      (libsource (lib "eagle-import") (part "FDG6316P"))
    )
    (comp (ref "U10")
      (value "FDG6316P")
      (footprint "eagle-import:SC70-6L")
      (libsource (lib "eagle-import") (part "FDG6316P"))
    )
    (comp (ref "U11")
      (value "FDG6316P")
      (footprint "eagle-import:SC70-6L")
      (libsource (lib "eagle-import") (part "FDG6316P"))
    )
    (comp (ref "U12")
      (value "FDG6316P")
      (footprint "eagle-import:SC70-6L")
      (libsource (lib "eagle-import") (part "FDG6316P"))
    )
    (comp (ref "BAT")
      (value "BATTERY")
      (footprint "eagle-import:BATTERY_AA_SMD")
      (libsource (lib "eagle-import") (part "BATTERY"))
    )
    (comp (ref "C6")
      (value "10uF")
      (footprint "eagle-import:C0805")
      (libsource (lib "eagle-import") (part "C-USC0805"))
    )
    (comp (ref "C9")
      (value "10uF")
      (footprint "eagle-import:C0805")
      (libsource (lib "eagle-import") (part "C-USC0805"))
    )
    (comp (ref "C10")
      (value "2.2nF")
      (footprint "eagle-import:C0603")
      (libsource (lib "eagle-import") (part "C-USC0603"))
    )
    (comp (ref "C12")
      (value "10uF")
      (footprint "eagle-import:C0805")
      (libsource (lib "eagle-import") (part "C-USC0805"))
    )
    (comp (ref "C16")
      (value "47pF")
      (footprint "eagle-import:C0402")
      (libsource (lib "eagle-import") (part "C-USC0402"))
    )
    (comp (ref "C17")
      (value "10uF")
      (footprint "eagle-import:C0805")
      (libsource (lib "eagle-import") (part "C-USC0805"))
    )
    (comp (ref "C18")
      (value "10uF")
      (footprint "eagle-import:C0805")
      (libsource (lib "eagle-import") (part "C-USC0805"))
    )
    (comp (ref "D1")
      (value "ORANGE")
      (footprint "eagle-import:CHIP-LED0603")
      (libsource (lib "eagle-import") (part "LEDCHIP-LED0603"))
    )
    (comp (ref "D2")
      (value "RB161M-20")
      (footprint "eagle-import:SOD-123")
      (libsource (lib "eagle-import") (part "DIODESOD-123"))
    )
    (comp (ref "D3")
      (value "RB161M-20")
      (footprint "eagle-import:SOD-123")
      (libsource (lib "eagle-import") (part "DIODESOD-123"))
    )
    (comp (ref "D4")
      (value "PURPLE")
      (footprint "eagle-import:CHIP-LED0603")
      (libsource (lib "eagle-import") (part "LEDCHIP-LED0603"))
    )
    (comp (ref "L1")
      (value "2.2uH")
      (footprint "eagle-import:INDUCTOR_CD43")
      (libsource (lib "eagle-import") (part "LCD43"))
    )
    (comp (ref "R10")
      (value "1")
      (footprint "eagle-import:R0603")
      (libsource (lib "eagle-import") (part "R-US_R0603"))
    )
    (comp (ref "R11")
      (value "47")
      (footprint "eagle-import:R0805")
      (libsource (lib "eagle-import") (part "R-US_R0805"))
    )
    (comp (ref "SJ1")
      (value "SOLDERJUMPERTRACE")
      (footprint "eagle-import:SJ_2S-TRACE")
      (libsource (lib "eagle-import") (part "SOLDERJUMPERTRACE"))
    )
    (comp (ref "SW1")
      (value "SWITCH_SPDT")
      (footprint "eagle-import:SWITCH_6P-2POS")
      (libsource (lib "eagle-import") (part "SWITCH_SPDT"))
    )
    (comp (ref "TP7")
      (value "PTR1B1,27")
      (footprint "eagle-import:B1,27")
      (libsource (lib "eagle-import") (part "PTR1B1,27"))
    )
    (comp (ref "TP8")
      (value "PTR1B1,27")
      (footprint "eagle-import:B1,27")
      (libsource (lib "eagle-import") (part "PTR1B1,27"))
    )
    (comp (ref "TP24")
      (value "PTR1B1,27")
      (footprint "eagle-import:B1,27")
      (libsource (lib "eagle-import") (part "PTR1B1,27"))
    )
    (comp (ref "U$8")
      (value "MP3401A")
      (footprint "eagle-import:SO08-150")
      (libsource (lib "eagle-import") (part "MP3401A"))
    )
    (comp (ref "U5")
      (value "MIC5219 3.3V")
      (footprint "eagle-import:SOT23-5")
      (libsource (lib "eagle-import") (part "V_REG_MIC52193.3V"))
    )
    (comp (ref "3.3V")
      (value "PTR1B2,54")
      (footprint "eagle-import:B2,54")
      (libsource (lib "eagle-import") (part "PTR1B2,54"))
    )
    (comp (ref "5")
      (value "PTR1B2,54")
      (footprint "eagle-import:B2,54")
      (libsource (lib "eagle-import") (part "PTR1B2,54"))
    )
    (comp (ref "16")
      (value "PTR1B2,54")
      (footprint "eagle-import:B2,54")
      (libsource (lib "eagle-import") (part "PTR1B2,54"))
    )
    (comp (ref "ANALOG_IN")
      (value "PTR1B2,54")
      (footprint "eagle-import:B2,54")
      (libsource (lib "eagle-import") (part "PTR1B2,54"))
    )
    (comp (ref "C13")
      (value "100nF")
      (footprint "eagle-import:C0402")
      (libsource (lib "eagle-import") (part "C-USC0402"))
    )
    (comp (ref "C14")
      (value "100nF")
      (footprint "eagle-import:C0402")
      (libsource (lib "eagle-import") (part "C-USC0402"))
    )
    (comp (ref "C15")
      (value "100nF")
      (footprint "eagle-import:C0402")
      (libsource (lib "eagle-import") (part "C-USC0402"))
    )
    (comp (ref "GROUND")
      (value "PTR1B2,54")
      (footprint "eagle-import:B2,54")
      (libsource (lib "eagle-import") (part "PTR1B2,54"))
    )
    (comp (ref "R12")
      (value "47k")
      (footprint "eagle-import:R0402")
      (libsource (lib "eagle-import") (part "R-US_R0402"))
    )
    (comp (ref "R17")
      (value "4.7k")
      (footprint "eagle-import:R0402")
      (libsource (lib "eagle-import") (part "R-US_R0402"))
    )
    (comp (ref "R18")
      (value "4.7k")
      (footprint "eagle-import:R0402")
      (libsource (lib "eagle-import") (part "R-US_R0402"))
    )
    (comp (ref "R23")
      (value "47k")
      (footprint "eagle-import:R0402")
      (libsource (lib "eagle-import") (part "R-US_R0402"))
    )
    (comp (ref "R25")
      (value "47k")
      (footprint "eagle-import:R0402")
      (libsource (lib "eagle-import") (part "R-US_R0402"))
    )
    (comp (ref "R26")
      (value "47k")
      (footprint "eagle-import:R0402")
      (libsource (lib "eagle-import") (part "R-US_R0402"))
    )
    (comp (ref "R27")
      (value "47k")
      (footprint "eagle-import:R0402")
      (libsource (lib "eagle-import") (part "R-US_R0402"))
    )
    (comp (ref "R28")
      (value "DNP")
      (footprint "eagle-import:R0402")
      (libsource (lib "eagle-import") (part "R-US_R0402"))
    )
    (comp (ref "SW2")
      (value "BRIGHTNESS")
      (footprint "eagle-import:TD-07XB")
      (libsource (lib "eagle-import") (part "BUTTON_MOMENTARY_GROUND"))
    )
    (comp (ref "TP5")
      (value "PTR1B1,27")
      (footprint "eagle-import:B1,27")
      (libsource (lib "eagle-import") (part "PTR1B1,27"))
    )
    (comp (ref "TP6")
      (value "PTR1B1,27")
      (footprint "eagle-import:B1,27")
      (libsource (lib "eagle-import") (part "PTR1B1,27"))
    )
    (comp (ref "TP15")
      (value "PTR1B1,27")
      (footprint "eagle-import:B1,27")
      (libsource (lib "eagle-import") (part "PTR1B1,27"))
    )
    (comp (ref "TP17")
      (value "PTR1B1,27")
      (footprint "eagle-import:B1,27")
      (libsource (lib "eagle-import") (part "PTR1B1,27"))
    )
    (comp (ref "TP23")
      (value "PTR1B1,27")
      (footprint "eagle-import:B1,27")
      (libsource (lib "eagle-import") (part "PTR1B1,27"))
    )
    (comp (ref "TP25")
      (value "PTR1B1,27")
      (footprint "eagle-import:B1,27")
      (libsource (lib "eagle-import") (part "PTR1B1,27"))
    )
    (comp (ref "U6")
      (value "ESP_WROOM_02")
      (footprint "eagle-import:ESP_WROOM_02")
      (libsource (lib "eagle-import") (part "ESP_WROOM_02"))
    )
    (comp (ref "U8")
      (value "MMA8653FC")
      (footprint "eagle-import:VFDFN-10")
      (libsource (lib "eagle-import") (part "MMA8653FC"))
    )
  )
  (nets
    (net (code "1") (name "+3V3") (class "Default")
      (node (ref "3.3V") (pin "TP") (pinfunction "TP_TP") (pintype "input"))
      (node (ref "C14") (pin "1") (pinfunction "1_1") (pintype "passive"))
      (node (ref "C15") (pin "1") (pinfunction "1_1") (pintype "passive"))
      (node (ref "C6") (pin "1") (pinfunction "1_1") (pintype "passive"))
      (node (ref "R12") (pin "2") (pinfunction "2_2") (pintype "passive"))
      (node (ref "R17") (pin "2") (pinfunction "2_2") (pintype "passive"))
      (node (ref "R18") (pin "2") (pinfunction "2_2") (pintype "passive"))
      (node (ref "R23") (pin "2") (pinfunction "2_2") (pintype "passive"))
      (node (ref "R26") (pin "2") (pinfunction "2_2") (pintype "passive"))
      (node (ref "R27") (pin "2") (pinfunction "2_2") (pintype "passive"))
      (node (ref "R28") (pin "2") (pinfunction "2_2") (pintype "passive"))
      (node (ref "U5") (pin "5") (pinfunction "OUT_5") (pintype "passive"))
      (node (ref "U6") (pin "3V3") (pinfunction "3V3_3V3") (pintype "bidirectional"))
      (node (ref "U8") (pin "P$1") (pinfunction "VDD_P$1") (pintype "bidirectional"))
      (node (ref "U8") (pin "P$8") (pinfunction "VDDIO_P$8") (pintype "bidirectional"))
    )
    (net (code "2") (name "+5V") (class "Default")
      (node (ref "C18") (pin "1") (pinfunction "1_1") (pintype "passive"))
      (node (ref "C4") (pin "1") (pinfunction "1_1") (pintype "passive"))
      (node (ref "C8") (pin "1") (pinfunction "1_1") (pintype "passive"))
      (node (ref "SW1") (pin "P0") (pinfunction "P_P0") (pintype "passive"))
      (node (ref "SW1") (pin "P1") (pinfunction "P_P1") (pintype "passive"))
      (node (ref "TP7") (pin "TP") (pinfunction "TP_TP") (pintype "input"))
      (node (ref "U1") (pin "6") (pinfunction "VREGIN_6") (pintype "bidirectional"))
      (node (ref "U10") (pin "1") (pinfunction "S_1") (pintype "passive"))
      (node (ref "U10") (pin "4") (pinfunction "S_4") (pintype "passive"))
      (node (ref "U11") (pin "1") (pinfunction "S_1") (pintype "passive"))
      (node (ref "U11") (pin "4") (pinfunction "S_4") (pintype "passive"))
      (node (ref "U12") (pin "1") (pinfunction "S_1") (pintype "passive"))
      (node (ref "U12") (pin "4") (pinfunction "S_4") (pintype "passive"))
      (node (ref "U3") (pin "16") (pinfunction "VCC_16") (pintype "power_in"))
      (node (ref "U5") (pin "1") (pinfunction "IN_1") (pintype "input"))
      (node (ref "U5") (pin "3") (pinfunction "EN_3") (pintype "input"))
      (node (ref "U9") (pin "1") (pinfunction "S_1") (pintype "passive"))
      (node (ref "U9") (pin "4") (pinfunction "S_4") (pintype "passive"))
    )
    (net (code "3") (name "1ROW0") (class "Default")
      (node (ref "LED_1") (pin "2") (pinfunction "VCC_2") (pintype "bidirectional"))
      (node (ref "LED_2") (pin "2") (pinfunction "VCC_2") (pintype "bidirectional"))
      (node (ref "LED_3") (pin "2") (pinfunction "VCC_2") (pintype "bidirectional"))
      (node (ref "LED_4") (pin "2") (pinfunction "VCC_2") (pintype "bidirectional"))
      (node (ref "LED_5") (pin "2") (pinfunction "VCC_2") (pintype "bidirectional"))
      (node (ref "LED_6") (pin "2") (pinfunction "VCC_2") (pintype "bidirectional"))
      (node (ref "LED_7") (pin "2") (pinfunction "VCC_2") (pintype "bidirectional"))
      (node (ref "LED_8") (pin "2") (pinfunction "VCC_2") (pintype "bidirectional"))
      (node (ref "R2") (pin "2") (pinfunction "2_2") (pintype "passive"))
      (node (ref "U10") (pin "6") (pinfunction "D_6") (pintype "passive"))
    )
    (net (code "4") (name "1ROW1") (class "Default")
      (node (ref "LED_10") (pin "2") (pinfunction "VCC_2") (pintype "bidirectional"))
      (node (ref "LED_11") (pin "2") (pinfunction "VCC_2") (pintype "bidirectional"))
      (node (ref "LED_12") (pin "2") (pinfunction "VCC_2") (pintype "bidirectional"))
      (node (ref "LED_13") (pin "2") (pinfunction "VCC_2") (pintype "bidirectional"))
      (node (ref "LED_14") (pin "2") (pinfunction "VCC_2") (pintype "bidirectional"))
      (node (ref "LED_15") (pin "2") (pinfunction "VCC_2") (pintype "bidirectional"))
      (node (ref "LED_16") (pin "2") (pinfunction "VCC_2") (pintype "bidirectional"))
      (node (ref "LED_9") (pin "2") (pinfunction "VCC_2") (pintype "bidirectional"))
      (node (ref "R3") (pin "2") (pinfunction "2_2") (pintype "passive"))
      (node (ref "U10") (pin "3") (pinfunction "D_3") (pintype "passive"))
    )
    (net (code "5") (name "1ROW2") (class "Default")
      (node (ref "LED_17") (pin "2") (pinfunction "VCC_2") (pintype "bidirectional"))
      (node (ref "LED_18") (pin "2") (pinfunction "VCC_2") (pintype "bidirectional"))
      (node (ref "LED_19") (pin "2") (pinfunction "VCC_2") (pintype "bidirectional"))
      (node (ref "LED_20") (pin "2") (pinfunction "VCC_2") (pintype "bidirectional"))
      (node (ref "LED_21") (pin "2") (pinfunction "VCC_2") (pintype "bidirectional"))
      (node (ref "LED_22") (pin "2") (pinfunction "VCC_2") (pintype "bidirectional"))
      (node (ref "LED_23") (pin "2") (pinfunction "VCC_2") (pintype "bidirectional"))
      (node (ref "LED_24") (pin "2") (pinfunction "VCC_2") (pintype "bidirectional"))
      (node (ref "R4") (pin "2") (pinfunction "2_2") (pintype "passive"))
      (node (ref "U9") (pin "6") (pinfunction "D_6") (pintype "passive"))
    )
    (net (code "6") (name "1ROW3") (class "Default")
      (node (ref "LED_25") (pin "2") (pinfunction "VCC_2") (pintype "bidirectional"))
      (node (ref "LED_26") (pin "2") (pinfunction "VCC_2") (pintype "bidirectional"))
      (node (ref "LED_27") (pin "2") (pinfunction "VCC_2") (pintype "bidirectional"))
      (node (ref "LED_28") (pin "2") (pinfunction "VCC_2") (pintype "bidirectional"))
      (node (ref "LED_29") (pin "2") (pinfunction "VCC_2") (pintype "bidirectional"))
      (node (ref "LED_30") (pin "2") (pinfunction "VCC_2") (pintype "bidirectional"))
      (node (ref "LED_31") (pin "2") (pinfunction "VCC_2") (pintype "bidirectional"))
      (node (ref "LED_32") (pin "2") (pinfunction "VCC_2") (pintype "bidirectional"))
      (node (ref "R5") (pin "2") (pinfunction "2_2") (pintype "passive"))
      (node (ref "U9") (pin "3") (pinfunction "D_3") (pintype "passive"))
    )
    (net (code "7") (name "1ROW4") (class "Default")
      (node (ref "LED_33") (pin "2") (pinfunction "VCC_2") (pintype "bidirectional"))
      (node (ref "LED_34") (pin "2") (pinfunction "VCC_2") (pintype "bidirectional"))
      (node (ref "LED_35") (pin "2") (pinfunction "VCC_2") (pintype "bidirectional"))
      (node (ref "LED_36") (pin "2") (pinfunction "VCC_2") (pintype "bidirectional"))
      (node (ref "LED_37") (pin "2") (pinfunction "VCC_2") (pintype "bidirectional"))
      (node (ref "LED_38") (pin "2") (pinfunction "VCC_2") (pintype "bidirectional"))
      (node (ref "LED_39") (pin "2") (pinfunction "VCC_2") (pintype "bidirectional"))
      (node (ref "LED_40") (pin "2") (pinfunction "VCC_2") (pintype "bidirectional"))
      (node (ref "R13") (pin "2") (pinfunction "2_2") (pintype "passive"))
      (node (ref "U11") (pin "6") (pinfunction "D_6") (pintype "passive"))
    )
    (net (code "8") (name "1ROW5") (class "Default")
      (node (ref "LED_41") (pin "2") (pinfunction "VCC_2") (pintype "bidirectional"))
      (node (ref "LED_42") (pin "2") (pinfunction "VCC_2") (pintype "bidirectional"))
      (node (ref "LED_43") (pin "2") (pinfunction "VCC_2") (pintype "bidirectional"))
      (node (ref "LED_44") (pin "2") (pinfunction "VCC_2") (pintype "bidirectional"))
      (node (ref "LED_45") (pin "2") (pinfunction "VCC_2") (pintype "bidirectional"))
      (node (ref "LED_46") (pin "2") (pinfunction "VCC_2") (pintype "bidirectional"))
      (node (ref "LED_47") (pin "2") (pinfunction "VCC_2") (pintype "bidirectional"))
      (node (ref "LED_48") (pin "2") (pinfunction "VCC_2") (pintype "bidirectional"))
      (node (ref "R14") (pin "2") (pinfunction "2_2") (pintype "passive"))
      (node (ref "U11") (pin "3") (pinfunction "D_3") (pintype "passive"))
    )
    (net (code "9") (name "1ROW6") (class "Default")
      (node (ref "LED_49") (pin "2") (pinfunction "VCC_2") (pintype "bidirectional"))
      (node (ref "LED_50") (pin "2") (pinfunction "VCC_2") (pintype "bidirectional"))
      (node (ref "LED_51") (pin "2") (pinfunction "VCC_2") (pintype "bidirectional"))
      (node (ref "LED_52") (pin "2") (pinfunction "VCC_2") (pintype "bidirectional"))
      (node (ref "LED_53") (pin "2") (pinfunction "VCC_2") (pintype "bidirectional"))
      (node (ref "LED_54") (pin "2") (pinfunction "VCC_2") (pintype "bidirectional"))
      (node (ref "LED_55") (pin "2") (pinfunction "VCC_2") (pintype "bidirectional"))
      (node (ref "LED_56") (pin "2") (pinfunction "VCC_2") (pintype "bidirectional"))
      (node (ref "R15") (pin "2") (pinfunction "2_2") (pintype "passive"))
      (node (ref "U12") (pin "6") (pinfunction "D_6") (pintype "passive"))
    )
    (net (code "10") (name "1ROW7") (class "Default")
      (node (ref "LED_57") (pin "2") (pinfunction "VCC_2") (pintype "bidirectional"))
      (node (ref "LED_58") (pin "2") (pinfunction "VCC_2") (pintype "bidirectional"))
      (node (ref "LED_59") (pin "2") (pinfunction "VCC_2") (pintype "bidirectional"))
      (node (ref "LED_60") (pin "2") (pinfunction "VCC_2") (pintype "bidirectional"))
      (node (ref "LED_61") (pin "2") (pinfunction "VCC_2") (pintype "bidirectional"))
      (node (ref "LED_62") (pin "2") (pinfunction "VCC_2") (pintype "bidirectional"))
      (node (ref "LED_63") (pin "2") (pinfunction "VCC_2") (pintype "bidirectional"))
      (node (ref "LED_64") (pin "2") (pinfunction "VCC_2") (pintype "bidirectional"))
      (node (ref "R16") (pin "2") (pinfunction "2_2") (pintype "passive"))
      (node (ref "U12") (pin "3") (pinfunction "D_3") (pintype "passive"))
    )
    (net (code "11") (name "ACC_INT1") (class "Default")
      (node (ref "U6") (pin "IO13") (pinfunction "IO13_IO13") (pintype "bidirectional"))
      (node (ref "U8") (pin "P$3") (pinfunction "INT1_P$3") (pintype "bidirectional"))
    )
    (net (code "12") (name "ARM_3V3") (class "Default")
      (node (ref "C1") (pin "1") (pinfunction "1_1") (pintype "passive"))
      (node (ref "C11") (pin "1") (pinfunction "1_1") (pintype "passive"))
      (node (ref "C2") (pin "1") (pinfunction "1_1") (pintype "passive"))
      (node (ref "C3") (pin "1") (pinfunction "1_1") (pintype "passive"))
      (node (ref "C5") (pin "1") (pinfunction "1_1") (pintype "passive"))
      (node (ref "C7") (pin "1") (pinfunction "1_1") (pintype "passive"))
      (node (ref "R6") (pin "2") (pinfunction "2_2") (pintype "passive"))
      (node (ref "TP9") (pin "TP") (pinfunction "TP_TP") (pintype "input"))
      (node (ref "U1") (pin "1") (pinfunction "VDD_1") (pintype "bidirectional"))
      (node (ref "U1") (pin "11") (pinfunction "VBAT_11") (pintype "bidirectional"))
      (node (ref "U1") (pin "5") (pinfunction "VOUT33_5") (pintype "bidirectional"))
      (node (ref "U1") (pin "7") (pinfunction "VDDA_7") (pintype "bidirectional"))
      (node (ref "U2") (pin "24") (pinfunction "VCC_24") (pintype "bidirectional"))
      (node (ref "U4") (pin "24") (pinfunction "VCC_24") (pintype "bidirectional"))
    )
    (net (code "13") (name "ARM_BOOTLOADER") (class "Default")
      (node (ref "TP16") (pin "TP") (pinfunction "TP_TP") (pintype "input"))
      (node (ref "U1") (pin "25") (pinfunction "PTC4_25") (pintype "bidirectional"))
    )
    (net (code "14") (name "ARM_RESET") (class "Default")
      (node (ref "TP14") (pin "TP") (pinfunction "TP_TP") (pintype "input"))
      (node (ref "U1") (pin "19") (pinfunction "RESET_B_19") (pintype "bidirectional"))
    )
    (net (code "15") (name "ARM_RX") (class "Default")
      (node (ref "TP13") (pin "TP") (pinfunction "TP_TP") (pintype "input"))
      (node (ref "U1") (pin "13") (pinfunction "PTA1_13") (pintype "bidirectional"))
      (node (ref "U6") (pin "TXD") (pinfunction "TXD_TXD") (pintype "bidirectional"))
    )
    (net (code "16") (name "ARM_RX1") (class "Default")
      (node (ref "R12") (pin "1") (pinfunction "1_1") (pintype "passive"))
      (node (ref "TP23") (pin "TP") (pinfunction "TP_TP") (pintype "input"))
      (node (ref "U1") (pin "24") (pinfunction "PTC3_24") (pintype "bidirectional"))
      (node (ref "U6") (pin "IO2") (pinfunction "IO2_IO2") (pintype "bidirectional"))
    )
    (net (code "17") (name "ARM_TCK") (class "Default")
      (node (ref "TP11") (pin "TP") (pinfunction "TP_TP") (pintype "input"))
      (node (ref "U1") (pin "12") (pinfunction "PTA0_12") (pintype "bidirectional"))
    )
    (net (code "18") (name "ARM_TMS") (class "Default")
      (node (ref "TP10") (pin "TP") (pinfunction "TP_TP") (pintype "input"))
      (node (ref "U1") (pin "15") (pinfunction "PTA3_15") (pintype "bidirectional"))
    )
    (net (code "19") (name "ARM_TX") (class "Default")
      (node (ref "TP12") (pin "TP") (pinfunction "TP_TP") (pintype "input"))
      (node (ref "U1") (pin "14") (pinfunction "PTA2_14") (pintype "bidirectional"))
      (node (ref "U6") (pin "RXD") (pinfunction "RXD_RXD") (pintype "bidirectional"))
    )
    (net (code "20") (name "BCOL0") (class "Default")
      (node (ref "LED_1") (pin "3") (pinfunction "BLUE_3") (pintype "bidirectional"))
      (node (ref "LED_17") (pin "3") (pinfunction "BLUE_3") (pintype "bidirectional"))
      (node (ref "LED_25") (pin "3") (pinfunction "BLUE_3") (pintype "bidirectional"))
      (node (ref "LED_33") (pin "3") (pinfunction "BLUE_3") (pintype "bidirectional"))
      (node (ref "LED_41") (pin "3") (pinfunction "BLUE_3") (pintype "bidirectional"))
      (node (ref "LED_49") (pin "3") (pinfunction "BLUE_3") (pintype "bidirectional"))
      (node (ref "LED_57") (pin "3") (pinfunction "BLUE_3") (pintype "bidirectional"))
      (node (ref "LED_9") (pin "3") (pinfunction "BLUE_3") (pintype "bidirectional"))
      (node (ref "U2") (pin "13") (pinfunction "OUT8_13") (pintype "bidirectional"))
    )
    (net (code "21") (name "BCOL1") (class "Default")
      (node (ref "LED_10") (pin "3") (pinfunction "BLUE_3") (pintype "bidirectional"))
      (node (ref "LED_18") (pin "3") (pinfunction "BLUE_3") (pintype "bidirectional"))
      (node (ref "LED_2") (pin "3") (pinfunction "BLUE_3") (pintype "bidirectional"))
      (node (ref "LED_26") (pin "3") (pinfunction "BLUE_3") (pintype "bidirectional"))
      (node (ref "LED_34") (pin "3") (pinfunction "BLUE_3") (pintype "bidirectional"))
      (node (ref "LED_42") (pin "3") (pinfunction "BLUE_3") (pintype "bidirectional"))
      (node (ref "LED_50") (pin "3") (pinfunction "BLUE_3") (pintype "bidirectional"))
      (node (ref "LED_58") (pin "3") (pinfunction "BLUE_3") (pintype "bidirectional"))
      (node (ref "U2") (pin "14") (pinfunction "OUT9_14") (pintype "bidirectional"))
    )
    (net (code "22") (name "BCOL2") (class "Default")
      (node (ref "LED_11") (pin "3") (pinfunction "BLUE_3") (pintype "bidirectional"))
      (node (ref "LED_19") (pin "3") (pinfunction "BLUE_3") (pintype "bidirectional"))
      (node (ref "LED_27") (pin "3") (pinfunction "BLUE_3") (pintype "bidirectional"))
      (node (ref "LED_3") (pin "3") (pinfunction "BLUE_3") (pintype "bidirectional"))
      (node (ref "LED_35") (pin "3") (pinfunction "BLUE_3") (pintype "bidirectional"))
      (node (ref "LED_43") (pin "3") (pinfunction "BLUE_3") (pintype "bidirectional"))
      (node (ref "LED_51") (pin "3") (pinfunction "BLUE_3") (pintype "bidirectional"))
      (node (ref "LED_59") (pin "3") (pinfunction "BLUE_3") (pintype "bidirectional"))
      (node (ref "U2") (pin "15") (pinfunction "OUT10_15") (pintype "bidirectional"))
    )
    (net (code "23") (name "BCOL3") (class "Default")
      (node (ref "LED_12") (pin "3") (pinfunction "BLUE_3") (pintype "bidirectional"))
      (node (ref "LED_20") (pin "3") (pinfunction "BLUE_3") (pintype "bidirectional"))
      (node (ref "LED_28") (pin "3") (pinfunction "BLUE_3") (pintype "bidirectional"))
      (node (ref "LED_36") (pin "3") (pinfunction "BLUE_3") (pintype "bidirectional"))
      (node (ref "LED_4") (pin "3") (pinfunction "BLUE_3") (pintype "bidirectional"))
      (node (ref "LED_44") (pin "3") (pinfunction "BLUE_3") (pintype "bidirectional"))
      (node (ref "LED_52") (pin "3") (pinfunction "BLUE_3") (pintype "bidirectional"))
      (node (ref "LED_60") (pin "3") (pinfunction "BLUE_3") (pintype "bidirectional"))
      (node (ref "U2") (pin "16") (pinfunction "OUT11_16") (pintype "bidirectional"))
    )
    (net (code "24") (name "BCOL4") (class "Default")
      (node (ref "LED_13") (pin "3") (pinfunction "BLUE_3") (pintype "bidirectional"))
      (node (ref "LED_21") (pin "3") (pinfunction "BLUE_3") (pintype "bidirectional"))
      (node (ref "LED_29") (pin "3") (pinfunction "BLUE_3") (pintype "bidirectional"))
      (node (ref "LED_37") (pin "3") (pinfunction "BLUE_3") (pintype "bidirectional"))
      (node (ref "LED_45") (pin "3") (pinfunction "BLUE_3") (pintype "bidirectional"))
      (node (ref "LED_5") (pin "3") (pinfunction "BLUE_3") (pintype "bidirectional"))
      (node (ref "LED_53") (pin "3") (pinfunction "BLUE_3") (pintype "bidirectional"))
      (node (ref "LED_61") (pin "3") (pinfunction "BLUE_3") (pintype "bidirectional"))
      (node (ref "U2") (pin "17") (pinfunction "OUT12_17") (pintype "bidirectional"))
    )
    (net (code "25") (name "BCOL5") (class "Default")
      (node (ref "LED_14") (pin "3") (pinfunction "BLUE_3") (pintype "bidirectional"))
      (node (ref "LED_22") (pin "3") (pinfunction "BLUE_3") (pintype "bidirectional"))
      (node (ref "LED_30") (pin "3") (pinfunction "BLUE_3") (pintype "bidirectional"))
      (node (ref "LED_38") (pin "3") (pinfunction "BLUE_3") (pintype "bidirectional"))
      (node (ref "LED_46") (pin "3") (pinfunction "BLUE_3") (pintype "bidirectional"))
      (node (ref "LED_54") (pin "3") (pinfunction "BLUE_3") (pintype "bidirectional"))
      (node (ref "LED_6") (pin "3") (pinfunction "BLUE_3") (pintype "bidirectional"))
      (node (ref "LED_62") (pin "3") (pinfunction "BLUE_3") (pintype "bidirectional"))
      (node (ref "U2") (pin "18") (pinfunction "OUT13_18") (pintype "bidirectional"))
    )
    (net (code "26") (name "BCOL6") (class "Default")
      (node (ref "LED_15") (pin "3") (pinfunction "BLUE_3") (pintype "bidirectional"))
      (node (ref "LED_23") (pin "3") (pinfunction "BLUE_3") (pintype "bidirectional"))
      (node (ref "LED_31") (pin "3") (pinfunction "BLUE_3") (pintype "bidirectional"))
      (node (ref "LED_39") (pin "3") (pinfunction "BLUE_3") (pintype "bidirectional"))
      (node (ref "LED_47") (pin "3") (pinfunction "BLUE_3") (pintype "bidirectional"))
      (node (ref "LED_55") (pin "3") (pinfunction "BLUE_3") (pintype "bidirectional"))
      (node (ref "LED_63") (pin "3") (pinfunction "BLUE_3") (pintype "bidirectional"))
      (node (ref "LED_7") (pin "3") (pinfunction "BLUE_3") (pintype "bidirectional"))
      (node (ref "U2") (pin "19") (pinfunction "OUT14_19") (pintype "bidirectional"))
    )
    (net (code "27") (name "BCOL7") (class "Default")
      (node (ref "LED_16") (pin "3") (pinfunction "BLUE_3") (pintype "bidirectional"))
      (node (ref "LED_24") (pin "3") (pinfunction "BLUE_3") (pintype "bidirectional"))
      (node (ref "LED_32") (pin "3") (pinfunction "BLUE_3") (pintype "bidirectional"))
      (node (ref "LED_40") (pin "3") (pinfunction "BLUE_3") (pintype "bidirectional"))
      (node (ref "LED_48") (pin "3") (pinfunction "BLUE_3") (pintype "bidirectional"))
      (node (ref "LED_56") (pin "3") (pinfunction "BLUE_3") (pintype "bidirectional"))
      (node (ref "LED_64") (pin "3") (pinfunction "BLUE_3") (pintype "bidirectional"))
      (node (ref "LED_8") (pin "3") (pinfunction "BLUE_3") (pintype "bidirectional"))
      (node (ref "U2") (pin "20") (pinfunction "OUT15_20") (pintype "bidirectional"))
    )
    (net (code "28") (name "BOOST_5V") (class "Default")
      (node (ref "C9") (pin "1") (pinfunction "1_1") (pintype "passive"))
      (node (ref "D2") (pin "A") (pinfunction "A_A") (pintype "passive"))
      (node (ref "TP24") (pin "TP") (pinfunction "TP_TP") (pintype "input"))
      (node (ref "U$8") (pin "8") (pinfunction "OUT_8") (pintype "bidirectional"))
    )
    (net (code "29") (name "BUTTON") (class "Default")
      (node (ref "R28") (pin "1") (pinfunction "1_1") (pintype "passive"))
      (node (ref "SW2") (pin "1") (pinfunction "P_1") (pintype "passive"))
      (node (ref "SW2") (pin "2") (pinfunction "P_2") (pintype "passive"))
      (node (ref "TP25") (pin "TP") (pinfunction "TP_TP") (pintype "input"))
      (node (ref "U6") (pin "IO4") (pinfunction "IO4_IO4") (pintype "bidirectional"))
    )
    (net (code "30") (name "CHARGE") (class "Default")
      (node (ref "D1") (pin "A") (pinfunction "A_A") (pintype "passive"))
      (node (ref "U$8") (pin "6") (pinfunction "LED2_6") (pintype "bidirectional"))
    )
    (net (code "31") (name "DISCHARGE") (class "Default")
      (node (ref "D4") (pin "A") (pinfunction "A_A") (pintype "passive"))
      (node (ref "U$8") (pin "5") (pinfunction "LED1_5") (pintype "bidirectional"))
    )
    (net (code "32") (name "ESP_GPIO0") (class "Default")
      (node (ref "R23") (pin "1") (pinfunction "1_1") (pintype "passive"))
      (node (ref "TP15") (pin "TP") (pinfunction "TP_TP") (pintype "input"))
      (node (ref "U1") (pin "21") (pinfunction "PTB1_21") (pintype "bidirectional"))
      (node (ref "U6") (pin "IO0") (pinfunction "IO0_IO0") (pintype "bidirectional"))
    )
    (net (code "33") (name "ESP_GPIO15") (class "Default")
      (node (ref "R25") (pin "2") (pinfunction "2_2") (pintype "passive"))
      (node (ref "U6") (pin "IO15") (pinfunction "IO15_IO15") (pintype "bidirectional"))
    )
    (net (code "34") (name "ESP_GPIO16") (class "Default")
      (node (ref "16") (pin "TP") (pinfunction "TP_TP") (pintype "input"))
      (node (ref "U6") (pin "IO18") (pinfunction "IO18_IO18") (pintype "bidirectional"))
    )
    (net (code "35") (name "ESP_RESET") (class "Default")
      (node (ref "R27") (pin "1") (pinfunction "1_1") (pintype "passive"))
      (node (ref "TP17") (pin "TP") (pinfunction "TP_TP") (pintype "input"))
      (node (ref "U1") (pin "20") (pinfunction "PTB0_20") (pintype "bidirectional"))
      (node (ref "U6") (pin "RST") (pinfunction "RST_RST") (pintype "bidirectional"))
    )
    (net (code "36") (name "ESP_TOUT") (class "Default")
      (node (ref "ANALOG_IN") (pin "TP") (pinfunction "TP_TP") (pintype "input"))
      (node (ref "U6") (pin "TOUT") (pinfunction "TOUT_TOUT") (pintype "bidirectional"))
    )
    (net (code "37") (name "EXP_GPIO5") (class "Default")
      (node (ref "5") (pin "TP") (pinfunction "TP_TP") (pintype "input"))
      (node (ref "U6") (pin "IO5") (pinfunction "IO5_IO5") (pintype "bidirectional"))
    )
    (net (code "38") (name "GCOL0") (class "Default")
      (node (ref "LED_1") (pin "4") (pinfunction "GREEN_4") (pintype "bidirectional"))
      (node (ref "LED_17") (pin "4") (pinfunction "GREEN_4") (pintype "bidirectional"))
      (node (ref "LED_25") (pin "4") (pinfunction "GREEN_4") (pintype "bidirectional"))
      (node (ref "LED_33") (pin "4") (pinfunction "GREEN_4") (pintype "bidirectional"))
      (node (ref "LED_41") (pin "4") (pinfunction "GREEN_4") (pintype "bidirectional"))
      (node (ref "LED_49") (pin "4") (pinfunction "GREEN_4") (pintype "bidirectional"))
      (node (ref "LED_57") (pin "4") (pinfunction "GREEN_4") (pintype "bidirectional"))
      (node (ref "LED_9") (pin "4") (pinfunction "GREEN_4") (pintype "bidirectional"))
      (node (ref "U4") (pin "5") (pinfunction "OUT0_5") (pintype "bidirectional"))
    )
    (net (code "39") (name "GCOL1") (class "Default")
      (node (ref "LED_10") (pin "4") (pinfunction "GREEN_4") (pintype "bidirectional"))
      (node (ref "LED_18") (pin "4") (pinfunction "GREEN_4") (pintype "bidirectional"))
      (node (ref "LED_2") (pin "4") (pinfunction "GREEN_4") (pintype "bidirectional"))
      (node (ref "LED_26") (pin "4") (pinfunction "GREEN_4") (pintype "bidirectional"))
      (node (ref "LED_34") (pin "4") (pinfunction "GREEN_4") (pintype "bidirectional"))
      (node (ref "LED_42") (pin "4") (pinfunction "GREEN_4") (pintype "bidirectional"))
      (node (ref "LED_50") (pin "4") (pinfunction "GREEN_4") (pintype "bidirectional"))
      (node (ref "LED_58") (pin "4") (pinfunction "GREEN_4") (pintype "bidirectional"))
      (node (ref "U4") (pin "6") (pinfunction "OUT1_6") (pintype "bidirectional"))
    )
    (net (code "40") (name "GCOL2") (class "Default")
      (node (ref "LED_11") (pin "4") (pinfunction "GREEN_4") (pintype "bidirectional"))
      (node (ref "LED_19") (pin "4") (pinfunction "GREEN_4") (pintype "bidirectional"))
      (node (ref "LED_27") (pin "4") (pinfunction "GREEN_4") (pintype "bidirectional"))
      (node (ref "LED_3") (pin "4") (pinfunction "GREEN_4") (pintype "bidirectional"))
      (node (ref "LED_35") (pin "4") (pinfunction "GREEN_4") (pintype "bidirectional"))
      (node (ref "LED_43") (pin "4") (pinfunction "GREEN_4") (pintype "bidirectional"))
      (node (ref "LED_51") (pin "4") (pinfunction "GREEN_4") (pintype "bidirectional"))
      (node (ref "LED_59") (pin "4") (pinfunction "GREEN_4") (pintype "bidirectional"))
      (node (ref "U4") (pin "7") (pinfunction "OUT2_7") (pintype "bidirectional"))
    )
    (net (code "41") (name "GCOL3") (class "Default")
      (node (ref "LED_12") (pin "4") (pinfunction "GREEN_4") (pintype "bidirectional"))
      (node (ref "LED_20") (pin "4") (pinfunction "GREEN_4") (pintype "bidirectional"))
      (node (ref "LED_28") (pin "4") (pinfunction "GREEN_4") (pintype "bidirectional"))
      (node (ref "LED_36") (pin "4") (pinfunction "GREEN_4") (pintype "bidirectional"))
      (node (ref "LED_4") (pin "4") (pinfunction "GREEN_4") (pintype "bidirectional"))
      (node (ref "LED_44") (pin "4") (pinfunction "GREEN_4") (pintype "bidirectional"))
      (node (ref "LED_52") (pin "4") (pinfunction "GREEN_4") (pintype "bidirectional"))
      (node (ref "LED_60") (pin "4") (pinfunction "GREEN_4") (pintype "bidirectional"))
      (node (ref "U4") (pin "8") (pinfunction "OUT3_8") (pintype "bidirectional"))
    )
    (net (code "42") (name "GCOL4") (class "Default")
      (node (ref "LED_13") (pin "4") (pinfunction "GREEN_4") (pintype "bidirectional"))
      (node (ref "LED_21") (pin "4") (pinfunction "GREEN_4") (pintype "bidirectional"))
      (node (ref "LED_29") (pin "4") (pinfunction "GREEN_4") (pintype "bidirectional"))
      (node (ref "LED_37") (pin "4") (pinfunction "GREEN_4") (pintype "bidirectional"))
      (node (ref "LED_45") (pin "4") (pinfunction "GREEN_4") (pintype "bidirectional"))
      (node (ref "LED_5") (pin "4") (pinfunction "GREEN_4") (pintype "bidirectional"))
      (node (ref "LED_53") (pin "4") (pinfunction "GREEN_4") (pintype "bidirectional"))
      (node (ref "LED_61") (pin "4") (pinfunction "GREEN_4") (pintype "bidirectional"))
      (node (ref "U4") (pin "9") (pinfunction "OUT4_9") (pintype "bidirectional"))
    )
    (net (code "43") (name "GCOL5") (class "Default")
      (node (ref "LED_14") (pin "4") (pinfunction "GREEN_4") (pintype "bidirectional"))
      (node (ref "LED_22") (pin "4") (pinfunction "GREEN_4") (pintype "bidirectional"))
      (node (ref "LED_30") (pin "4") (pinfunction "GREEN_4") (pintype "bidirectional"))
      (node (ref "LED_38") (pin "4") (pinfunction "GREEN_4") (pintype "bidirectional"))
      (node (ref "LED_46") (pin "4") (pinfunction "GREEN_4") (pintype "bidirectional"))
      (node (ref "LED_54") (pin "4") (pinfunction "GREEN_4") (pintype "bidirectional"))
      (node (ref "LED_6") (pin "4") (pinfunction "GREEN_4") (pintype "bidirectional"))
      (node (ref "LED_62") (pin "4") (pinfunction "GREEN_4") (pintype "bidirectional"))
      (node (ref "U4") (pin "10") (pinfunction "OUT5_10") (pintype "bidirectional"))
    )
    (net (code "44") (name "GCOL6") (class "Default")
      (node (ref "LED_15") (pin "4") (pinfunction "GREEN_4") (pintype "bidirectional"))
      (node (ref "LED_23") (pin "4") (pinfunction "GREEN_4") (pintype "bidirectional"))
      (node (ref "LED_31") (pin "4") (pinfunction "GREEN_4") (pintype "bidirectional"))
      (node (ref "LED_39") (pin "4") (pinfunction "GREEN_4") (pintype "bidirectional"))
      (node (ref "LED_47") (pin "4") (pinfunction "GREEN_4") (pintype "bidirectional"))
      (node (ref "LED_55") (pin "4") (pinfunction "GREEN_4") (pintype "bidirectional"))
      (node (ref "LED_63") (pin "4") (pinfunction "GREEN_4") (pintype "bidirectional"))
      (node (ref "LED_7") (pin "4") (pinfunction "GREEN_4") (pintype "bidirectional"))
      (node (ref "U4") (pin "11") (pinfunction "OUT6_11") (pintype "bidirectional"))
    )
    (net (code "45") (name "GCOL7") (class "Default")
      (node (ref "LED_16") (pin "4") (pinfunction "GREEN_4") (pintype "bidirectional"))
      (node (ref "LED_24") (pin "4") (pinfunction "GREEN_4") (pintype "bidirectional"))
      (node (ref "LED_32") (pin "4") (pinfunction "GREEN_4") (pintype "bidirectional"))
      (node (ref "LED_40") (pin "4") (pinfunction "GREEN_4") (pintype "bidirectional"))
      (node (ref "LED_48") (pin "4") (pinfunction "GREEN_4") (pintype "bidirectional"))
      (node (ref "LED_56") (pin "4") (pinfunction "GREEN_4") (pintype "bidirectional"))
      (node (ref "LED_64") (pin "4") (pinfunction "GREEN_4") (pintype "bidirectional"))
      (node (ref "LED_8") (pin "4") (pinfunction "GREEN_4") (pintype "bidirectional"))
      (node (ref "U4") (pin "12") (pinfunction "OUT7_12") (pintype "bidirectional"))
    )
    (net (code "46") (name "GND") (class "Default")
      (node (ref "BAT") (pin "-") (pinfunction "-_-") (pintype "bidirectional"))
      (node (ref "C1") (pin "2") (pinfunction "2_2") (pintype "passive"))
      (node (ref "C10") (pin "2") (pinfunction "2_2") (pintype "passive"))
      (node (ref "C11") (pin "2") (pinfunction "2_2") (pintype "passive"))
      (node (ref "C12") (pin "2") (pinfunction "2_2") (pintype "passive"))
      (node (ref "C13") (pin "2") (pinfunction "2_2") (pintype "passive"))
      (node (ref "C14") (pin "2") (pinfunction "2_2") (pintype "passive"))
      (node (ref "C15") (pin "2") (pinfunction "2_2") (pintype "passive"))
      (node (ref "C16") (pin "2") (pinfunction "2_2") (pintype "passive"))
      (node (ref "C17") (pin "2") (pinfunction "2_2") (pintype "passive"))
      (node (ref "C18") (pin "2") (pinfunction "2_2") (pintype "passive"))
      (node (ref "C2") (pin "2") (pinfunction "2_2") (pintype "passive"))
      (node (ref "C3") (pin "2") (pinfunction "2_2") (pintype "passive"))
      (node (ref "C4") (pin "2") (pinfunction "2_2") (pintype "passive"))
      (node (ref "C5") (pin "2") (pinfunction "2_2") (pintype "passive"))
      (node (ref "C6") (pin "2") (pinfunction "2_2") (pintype "passive"))
      (node (ref "C7") (pin "2") (pinfunction "2_2") (pintype "passive"))
      (node (ref "C8") (pin "2") (pinfunction "2_2") (pintype "passive"))
      (node (ref "C9") (pin "2") (pinfunction "2_2") (pintype "passive"))
      (node (ref "CON1") (pin "PAD$1") (pinfunction "SHIELD_PAD$1") (pintype "bidirectional"))
      (node (ref "CON1") (pin "PAD$10") (pinfunction "SHIELD_PAD$10") (pintype "bidirectional"))
      (node (ref "CON1") (pin "PAD$2") (pinfunction "SHIELD_PAD$2") (pintype "bidirectional"))
      (node (ref "CON1") (pin "PAD$3") (pinfunction "SHIELD_PAD$3") (pintype "bidirectional"))
      (node (ref "CON1") (pin "PAD$4") (pinfunction "SHIELD_PAD$4") (pintype "bidirectional"))
      (node (ref "CON1") (pin "PAD$5") (pinfunction "SHIELD_PAD$5") (pintype "bidirectional"))
      (node (ref "CON1") (pin "PAD$6") (pinfunction "SHIELD_PAD$6") (pintype "bidirectional"))
      (node (ref "CON1") (pin "PAD$7") (pinfunction "SHIELD_PAD$7") (pintype "bidirectional"))
      (node (ref "CON1") (pin "PAD$8") (pinfunction "SHIELD_PAD$8") (pintype "bidirectional"))
      (node (ref "CON1") (pin "PAD$9") (pinfunction "SHIELD_PAD$9") (pintype "bidirectional"))
      (node (ref "CON1") (pin "PIN$5") (pinfunction "GND_PIN$5") (pintype "bidirectional"))
      (node (ref "GROUND") (pin "TP") (pinfunction "TP_TP") (pintype "input"))
      (node (ref "Q1") (pin "P$2") (pinfunction "P$1_P$2") (pintype "bidirectional"))
      (node (ref "Q1") (pin "P$4") (pinfunction "P$1_P$4") (pintype "bidirectional"))
      (node (ref "R1") (pin "1") (pinfunction "1_1") (pintype "passive"))
      (node (ref "R11") (pin "1") (pinfunction "1_1") (pintype "passive"))
      (node (ref "R13") (pin "1") (pinfunction "1_1") (pintype "passive"))
      (node (ref "R14") (pin "1") (pinfunction "1_1") (pintype "passive"))
      (node (ref "R15") (pin "1") (pinfunction "1_1") (pintype "passive"))
      (node (ref "R16") (pin "1") (pinfunction "1_1") (pintype "passive"))
      (node (ref "R2") (pin "1") (pinfunction "1_1") (pintype "passive"))
      (node (ref "R21") (pin "1") (pinfunction "1_1") (pintype "passive"))
      (node (ref "R25") (pin "1") (pinfunction "1_1") (pintype "passive"))
      (node (ref "R3") (pin "1") (pinfunction "1_1") (pintype "passive"))
      (node (ref "R4") (pin "1") (pinfunction "1_1") (pintype "passive"))
      (node (ref "R5") (pin "1") (pinfunction "1_1") (pintype "passive"))
      (node (ref "R9") (pin "1") (pinfunction "1_1") (pintype "passive"))
      (node (ref "SJ1") (pin "1") (pinfunction "1_1") (pintype "passive"))
      (node (ref "SW2") (pin "3") (pinfunction "S_3") (pintype "passive"))
      (node (ref "SW2") (pin "4") (pinfunction "S_4") (pintype "passive"))
      (node (ref "SW2") (pin "5") (pinfunction "SHIELD_5") (pintype "passive"))
      (node (ref "TP18") (pin "TP") (pinfunction "TP_TP") (pintype "input"))
      (node (ref "U$8") (pin "2") (pinfunction "PGND_2") (pintype "bidirectional"))
      (node (ref "U$8") (pin "7") (pinfunction "GND_7") (pintype "bidirectional"))
      (node (ref "U1") (pin "2") (pinfunction "VSS_2") (pintype "bidirectional"))
      (node (ref "U1") (pin "8") (pinfunction "VSSA_8") (pintype "bidirectional"))
      (node (ref "U1") (pin "PAD@1") (pinfunction "VSS_PAD@1") (pintype "bidirectional"))
      (node (ref "U1") (pin "PAD@11") (pinfunction "VSS_PAD@11") (pintype "bidirectional"))
      (node (ref "U1") (pin "PAD@4") (pinfunction "VSS_PAD@4") (pintype "bidirectional"))
      (node (ref "U1") (pin "PAD@9") (pinfunction "VSS_PAD@9") (pintype "bidirectional"))
      (node (ref "U2") (pin "1") (pinfunction "GND_1") (pintype "bidirectional"))
      (node (ref "U3") (pin "5") (pinfunction "G2B_5") (pintype "input"))
      (node (ref "U3") (pin "8") (pinfunction "GND_8") (pintype "power_in"))
      (node (ref "U4") (pin "1") (pinfunction "GND_1") (pintype "bidirectional"))
      (node (ref "U5") (pin "2") (pinfunction "GND_2") (pintype "input"))
      (node (ref "U6") (pin "GND$1") (pinfunction "GND_GND$1") (pintype "bidirectional"))
      (node (ref "U6") (pin "GND$2") (pinfunction "GND_GND$2") (pintype "bidirectional"))
      (node (ref "U6") (pin "GND$3") (pinfunction "GND_GND$3") (pintype "bidirectional"))
      (node (ref "U8") (pin "P$6") (pinfunction "GND_P$6") (pintype "bidirectional"))
      (node (ref "U8") (pin "P$7") (pinfunction "GND_P$7") (pintype "bidirectional"))
      (node (ref "U8") (pin "P$9") (pinfunction "GND_P$9") (pintype "bidirectional"))
      (node (ref "Z1") (pin "1") (pinfunction "1_1") (pintype "passive"))
      (node (ref "Z2") (pin "1") (pinfunction "1_1") (pintype "passive"))
      (node (ref "Z3") (pin "1") (pinfunction "1_1") (pintype "passive"))
    )
    (net (code "47") (name "I2C_SCL") (class "Default")
      (node (ref "R18") (pin "1") (pinfunction "1_1") (pintype "passive"))
      (node (ref "TP6") (pin "TP") (pinfunction "TP_TP") (pintype "input"))
      (node (ref "U6") (pin "IO14") (pinfunction "IO14_IO14") (pintype "bidirectional"))
      (node (ref "U8") (pin "P$2") (pinfunction "SCL_P$2") (pintype "bidirectional"))
    )
    (net (code "48") (name "I2C_SDA") (class "Default")
      (node (ref "R17") (pin "1") (pinfunction "1_1") (pintype "passive"))
      (node (ref "TP5") (pin "TP") (pinfunction "TP_TP") (pintype "input"))
      (node (ref "U6") (pin "IO12") (pinfunction "IO12_IO12") (pintype "bidirectional"))
      (node (ref "U8") (pin "P$10") (pinfunction "SDA_P$10") (pintype "bidirectional"))
    )
    (net (code "49") (name "LED_CLK") (class "Default")
      (node (ref "TP2") (pin "TP") (pinfunction "TP_TP") (pintype "input"))
      (node (ref "U1") (pin "26") (pinfunction "PTC5_26") (pintype "bidirectional"))
      (node (ref "U2") (pin "3") (pinfunction "CLK_3") (pintype "bidirectional"))
      (node (ref "U4") (pin "3") (pinfunction "CLK_3") (pintype "bidirectional"))
    )
    (net (code "50") (name "LED_DAT_0") (class "Default")
      (node (ref "TP1") (pin "TP") (pinfunction "TP_TP") (pintype "input"))
      (node (ref "U1") (pin "27") (pinfunction "PTC6_27") (pintype "bidirectional"))
      (node (ref "U2") (pin "2") (pinfunction "DIN_2") (pintype "bidirectional"))
    )
    (net (code "51") (name "LED_DAT_1") (class "Default")
      (node (ref "U2") (pin "22") (pinfunction "DOUT_22") (pintype "bidirectional"))
      (node (ref "U4") (pin "2") (pinfunction "DIN_2") (pintype "bidirectional"))
    )
    (net (code "52") (name "LED_HS_EN") (class "Default")
      (node (ref "R21") (pin "2") (pinfunction "2_2") (pintype "passive"))
      (node (ref "TP22") (pin "TP") (pinfunction "TP_TP") (pintype "input"))
      (node (ref "U1") (pin "22") (pinfunction "PTC1_22") (pintype "bidirectional"))
      (node (ref "U3") (pin "6") (pinfunction "G1_6") (pintype "input"))
    )
    (net (code "53") (name "LED_OE") (class "Default")
      (node (ref "R6") (pin "1") (pinfunction "1_1") (pintype "passive"))
      (node (ref "TP4") (pin "TP") (pinfunction "TP_TP") (pintype "input"))
      (node (ref "U1") (pin "16") (pinfunction "PTA4_16") (pintype "bidirectional"))
      (node (ref "U2") (pin "21") (pinfunction "OE_21") (pintype "bidirectional"))
      (node (ref "U3") (pin "4") (pinfunction "G2A_4") (pintype "input"))
      (node (ref "U4") (pin "21") (pinfunction "OE_21") (pintype "bidirectional"))
    )
    (net (code "54") (name "LED_ROW_A") (class "Default")
      (node (ref "TP19") (pin "TP") (pinfunction "TP_TP") (pintype "input"))
      (node (ref "U1") (pin "30") (pinfunction "PTD5_30") (pintype "bidirectional"))
      (node (ref "U3") (pin "1") (pinfunction "A_1") (pintype "input"))
    )
    (net (code "55") (name "LED_ROW_B") (class "Default")
      (node (ref "TP20") (pin "TP") (pinfunction "TP_TP") (pintype "input"))
      (node (ref "U1") (pin "31") (pinfunction "PTD6_31") (pintype "bidirectional"))
      (node (ref "U3") (pin "2") (pinfunction "B_2") (pintype "input"))
    )
    (net (code "56") (name "LED_ROW_C") (class "Default")
      (node (ref "TP21") (pin "TP") (pinfunction "TP_TP") (pintype "input"))
      (node (ref "U1") (pin "32") (pinfunction "PTD7_32") (pintype "bidirectional"))
      (node (ref "U3") (pin "3") (pinfunction "C_3") (pintype "input"))
    )
    (net (code "57") (name "LED_S0") (class "Default")
      (node (ref "U10") (pin "2") (pinfunction "G_2") (pintype "passive"))
      (node (ref "U3") (pin "15") (pinfunction "Y0_15") (pintype "output"))
    )
    (net (code "58") (name "LED_S1") (class "Default")
      (node (ref "U10") (pin "5") (pinfunction "G_5") (pintype "passive"))
      (node (ref "U3") (pin "14") (pinfunction "Y1_14") (pintype "output"))
    )
    (net (code "59") (name "LED_S2") (class "Default")
      (node (ref "U3") (pin "13") (pinfunction "Y2_13") (pintype "output"))
      (node (ref "U9") (pin "2") (pinfunction "G_2") (pintype "passive"))
    )
    (net (code "60") (name "LED_S3") (class "Default")
      (node (ref "U3") (pin "12") (pinfunction "Y3_12") (pintype "output"))
      (node (ref "U9") (pin "5") (pinfunction "G_5") (pintype "passive"))
    )
    (net (code "61") (name "LED_S4") (class "Default")
      (node (ref "U11") (pin "2") (pinfunction "G_2") (pintype "passive"))
      (node (ref "U3") (pin "11") (pinfunction "Y4_11") (pintype "output"))
    )
    (net (code "62") (name "LED_S5") (class "Default")
      (node (ref "U11") (pin "5") (pinfunction "G_5") (pintype "passive"))
      (node (ref "U3") (pin "10") (pinfunction "Y5_10") (pintype "output"))
    )
    (net (code "63") (name "LED_S6") (class "Default")
      (node (ref "U12") (pin "2") (pinfunction "G_2") (pintype "passive"))
      (node (ref "U3") (pin "9") (pinfunction "Y6_9") (pintype "output"))
    )
    (net (code "64") (name "LED_S7") (class "Default")
      (node (ref "U12") (pin "5") (pinfunction "G_5") (pintype "passive"))
      (node (ref "U3") (pin "7") (pinfunction "Y7_7") (pintype "output"))
    )
    (net (code "65") (name "LED_STB") (class "Default")
      (node (ref "TP3") (pin "TP") (pinfunction "TP_TP") (pintype "input"))
      (node (ref "U1") (pin "29") (pinfunction "PTD4_29") (pintype "bidirectional"))
      (node (ref "U2") (pin "4") (pinfunction "LATCH_4") (pintype "bidirectional"))
      (node (ref "U4") (pin "4") (pinfunction "LATCH_4") (pintype "bidirectional"))
    )
    (net (code "66") (name "Net-(C10-Pad1)") (class "Default")
      (node (ref "C10") (pin "1") (pinfunction "1_1") (pintype "passive"))
      (node (ref "R10") (pin "2") (pinfunction "2_2") (pintype "passive"))
    )
    (net (code "67") (name "Net-(CON1-D+)") (class "Default")
      (node (ref "CON1") (pin "PIN$3") (pinfunction "D+_PIN$3") (pintype "bidirectional"))
      (node (ref "R8") (pin "1") (pinfunction "1_1") (pintype "passive"))
      (node (ref "Z2") (pin "2") (pinfunction "2_2") (pintype "passive"))
    )
    (net (code "68") (name "Net-(CON1-D-)") (class "Default")
      (node (ref "CON1") (pin "PIN$2") (pinfunction "D-_PIN$2") (pintype "bidirectional"))
      (node (ref "R7") (pin "1") (pinfunction "1_1") (pintype "passive"))
      (node (ref "Z1") (pin "2") (pinfunction "2_2") (pintype "passive"))
    )
    (net (code "69") (name "Net-(D1-PadC)") (class "Default")
      (node (ref "D1") (pin "C") (pinfunction "C_C") (pintype "passive"))
      (node (ref "D4") (pin "C") (pinfunction "C_C") (pintype "passive"))
      (node (ref "SJ1") (pin "2") (pinfunction "2_2") (pintype "passive"))
    )
    (net (code "70") (name "Net-(D2-PadC)") (class "Default")
      (node (ref "D2") (pin "C") (pinfunction "C_C") (pintype "passive"))
      (node (ref "D3") (pin "C") (pinfunction "C_C") (pintype "passive"))
      (node (ref "SW1") (pin "S0") (pinfunction "S_S0") (pintype "passive"))
      (node (ref "SW1") (pin "S1") (pinfunction "S_S1") (pintype "passive"))
    )
    (net (code "71") (name "Net-(L1-2)") (class "Default")
      (node (ref "L1") (pin "P$2") (pinfunction "2_P$2") (pintype "passive"))
      (node (ref "R10") (pin "1") (pinfunction "1_1") (pintype "passive"))
      (node (ref "U$8") (pin "1") (pinfunction "LX_1") (pintype "bidirectional"))
    )
    (net (code "72") (name "Net-(Q1-1)") (class "Default")
      (node (ref "Q1") (pin "P$1") (pinfunction "1_P$1") (pintype "passive"))
      (node (ref "U1") (pin "18") (pinfunction "PTA19_18") (pintype "bidirectional"))
    )
    (net (code "73") (name "Net-(Q1-2)") (class "Default")
      (node (ref "Q1") (pin "P$3") (pinfunction "2_P$3") (pintype "passive"))
      (node (ref "U1") (pin "17") (pinfunction "PTA18_17") (pintype "bidirectional"))
    )
    (net (code "74") (name "Net-(R11-Pad2)") (class "Default")
      (node (ref "R11") (pin "2") (pinfunction "2_2") (pintype "passive"))
      (node (ref "SW1") (pin "O0") (pinfunction "O_O0") (pintype "passive"))
      (node (ref "SW1") (pin "O1") (pinfunction "O_O1") (pintype "passive"))
    )
    (net (code "75") (name "Net-(R19B-1)") (class "Default")
      (node (ref "R19") (pin "2") (pinfunction "1_2") (pintype "passive"))
      (node (ref "U2") (pin "7") (pinfunction "OUT2_7") (pintype "bidirectional"))
    )
    (net (code "76") (name "Net-(R19C-1)") (class "Default")
      (node (ref "R19") (pin "3") (pinfunction "1_3") (pintype "passive"))
      (node (ref "U2") (pin "6") (pinfunction "OUT1_6") (pintype "bidirectional"))
    )
    (net (code "77") (name "Net-(R19D-1)") (class "Default")
      (node (ref "R19") (pin "4") (pinfunction "1_4") (pintype "passive"))
      (node (ref "U2") (pin "5") (pinfunction "OUT0_5") (pintype "bidirectional"))
    )
    (net (code "78") (name "Net-(R20B-1)") (class "Default")
      (node (ref "R20") (pin "2") (pinfunction "1_2") (pintype "passive"))
      (node (ref "U2") (pin "11") (pinfunction "OUT6_11") (pintype "bidirectional"))
    )
    (net (code "79") (name "Net-(R20C-1)") (class "Default")
      (node (ref "R20") (pin "3") (pinfunction "1_3") (pintype "passive"))
      (node (ref "U2") (pin "10") (pinfunction "OUT5_10") (pintype "bidirectional"))
    )
    (net (code "80") (name "Net-(R20D-1)") (class "Default")
      (node (ref "R20") (pin "4") (pinfunction "1_4") (pintype "passive"))
      (node (ref "U2") (pin "9") (pinfunction "OUT4_9") (pintype "bidirectional"))
    )
    (net (code "81") (name "Net-(R26-Pad1)") (class "Default")
      (node (ref "R26") (pin "1") (pinfunction "1_1") (pintype "passive"))
      (node (ref "U6") (pin "EN") (pinfunction "EN_EN") (pintype "bidirectional"))
    )
    (net (code "82") (name "Net-(U2-CREF)") (class "Default")
      (node (ref "R1") (pin "2") (pinfunction "2_2") (pintype "passive"))
      (node (ref "U2") (pin "23") (pinfunction "CREF_23") (pintype "bidirectional"))
    )
    (net (code "83") (name "Net-(U2-OUT3)") (class "Default")
      (node (ref "R19") (pin "1") (pinfunction "1_1") (pintype "passive"))
      (node (ref "U2") (pin "8") (pinfunction "OUT3_8") (pintype "bidirectional"))
    )
    (net (code "84") (name "Net-(U2-OUT7)") (class "Default")
      (node (ref "R20") (pin "1") (pinfunction "1_1") (pintype "passive"))
      (node (ref "U2") (pin "12") (pinfunction "OUT7_12") (pintype "bidirectional"))
    )
    (net (code "85") (name "Net-(U4-CREF)") (class "Default")
      (node (ref "R9") (pin "2") (pinfunction "2_2") (pintype "passive"))
      (node (ref "U4") (pin "23") (pinfunction "CREF_23") (pintype "bidirectional"))
    )
    (net (code "86") (name "Net-(U5-BP)") (class "Default")
      (node (ref "C16") (pin "1") (pinfunction "1_1") (pintype "passive"))
      (node (ref "U5") (pin "4") (pinfunction "BP_4") (pintype "input"))
    )
    (net (code "87") (name "Net-(U8-BYP)") (class "Default")
      (node (ref "C13") (pin "1") (pinfunction "1_1") (pintype "passive"))
      (node (ref "U8") (pin "P$4") (pinfunction "BYP_P$4") (pintype "bidirectional"))
    )
    (net (code "88") (name "RCOL0") (class "Default")
      (node (ref "LED_1") (pin "1") (pinfunction "RED_1") (pintype "bidirectional"))
      (node (ref "LED_17") (pin "1") (pinfunction "RED_1") (pintype "bidirectional"))
      (node (ref "LED_25") (pin "1") (pinfunction "RED_1") (pintype "bidirectional"))
      (node (ref "LED_33") (pin "1") (pinfunction "RED_1") (pintype "bidirectional"))
      (node (ref "LED_41") (pin "1") (pinfunction "RED_1") (pintype "bidirectional"))
      (node (ref "LED_49") (pin "1") (pinfunction "RED_1") (pintype "bidirectional"))
      (node (ref "LED_57") (pin "1") (pinfunction "RED_1") (pintype "bidirectional"))
      (node (ref "LED_9") (pin "1") (pinfunction "RED_1") (pintype "bidirectional"))
      (node (ref "R19") (pin "5") (pinfunction "2_5") (pintype "passive"))
    )
    (net (code "89") (name "RCOL1") (class "Default")
      (node (ref "LED_10") (pin "1") (pinfunction "RED_1") (pintype "bidirectional"))
      (node (ref "LED_18") (pin "1") (pinfunction "RED_1") (pintype "bidirectional"))
      (node (ref "LED_2") (pin "1") (pinfunction "RED_1") (pintype "bidirectional"))
      (node (ref "LED_26") (pin "1") (pinfunction "RED_1") (pintype "bidirectional"))
      (node (ref "LED_34") (pin "1") (pinfunction "RED_1") (pintype "bidirectional"))
      (node (ref "LED_42") (pin "1") (pinfunction "RED_1") (pintype "bidirectional"))
      (node (ref "LED_50") (pin "1") (pinfunction "RED_1") (pintype "bidirectional"))
      (node (ref "LED_58") (pin "1") (pinfunction "RED_1") (pintype "bidirectional"))
      (node (ref "R19") (pin "6") (pinfunction "2_6") (pintype "passive"))
    )
    (net (code "90") (name "RCOL2") (class "Default")
      (node (ref "LED_11") (pin "1") (pinfunction "RED_1") (pintype "bidirectional"))
      (node (ref "LED_19") (pin "1") (pinfunction "RED_1") (pintype "bidirectional"))
      (node (ref "LED_27") (pin "1") (pinfunction "RED_1") (pintype "bidirectional"))
      (node (ref "LED_3") (pin "1") (pinfunction "RED_1") (pintype "bidirectional"))
      (node (ref "LED_35") (pin "1") (pinfunction "RED_1") (pintype "bidirectional"))
      (node (ref "LED_43") (pin "1") (pinfunction "RED_1") (pintype "bidirectional"))
      (node (ref "LED_51") (pin "1") (pinfunction "RED_1") (pintype "bidirectional"))
      (node (ref "LED_59") (pin "1") (pinfunction "RED_1") (pintype "bidirectional"))
      (node (ref "R19") (pin "7") (pinfunction "2_7") (pintype "passive"))
    )
    (net (code "91") (name "RCOL3") (class "Default")
      (node (ref "LED_12") (pin "1") (pinfunction "RED_1") (pintype "bidirectional"))
      (node (ref "LED_20") (pin "1") (pinfunction "RED_1") (pintype "bidirectional"))
      (node (ref "LED_28") (pin "1") (pinfunction "RED_1") (pintype "bidirectional"))
      (node (ref "LED_36") (pin "1") (pinfunction "RED_1") (pintype "bidirectional"))
      (node (ref "LED_4") (pin "1") (pinfunction "RED_1") (pintype "bidirectional"))
      (node (ref "LED_44") (pin "1") (pinfunction "RED_1") (pintype "bidirectional"))
      (node (ref "LED_52") (pin "1") (pinfunction "RED_1") (pintype "bidirectional"))
      (node (ref "LED_60") (pin "1") (pinfunction "RED_1") (pintype "bidirectional"))
      (node (ref "R19") (pin "8") (pinfunction "2_8") (pintype "passive"))
    )
    (net (code "92") (name "RCOL4") (class "Default")
      (node (ref "LED_13") (pin "1") (pinfunction "RED_1") (pintype "bidirectional"))
      (node (ref "LED_21") (pin "1") (pinfunction "RED_1") (pintype "bidirectional"))
      (node (ref "LED_29") (pin "1") (pinfunction "RED_1") (pintype "bidirectional"))
      (node (ref "LED_37") (pin "1") (pinfunction "RED_1") (pintype "bidirectional"))
      (node (ref "LED_45") (pin "1") (pinfunction "RED_1") (pintype "bidirectional"))
      (node (ref "LED_5") (pin "1") (pinfunction "RED_1") (pintype "bidirectional"))
      (node (ref "LED_53") (pin "1") (pinfunction "RED_1") (pintype "bidirectional"))
      (node (ref "LED_61") (pin "1") (pinfunction "RED_1") (pintype "bidirectional"))
      (node (ref "R20") (pin "5") (pinfunction "2_5") (pintype "passive"))
    )
    (net (code "93") (name "RCOL5") (class "Default")
      (node (ref "LED_14") (pin "1") (pinfunction "RED_1") (pintype "bidirectional"))
      (node (ref "LED_22") (pin "1") (pinfunction "RED_1") (pintype "bidirectional"))
      (node (ref "LED_30") (pin "1") (pinfunction "RED_1") (pintype "bidirectional"))
      (node (ref "LED_38") (pin "1") (pinfunction "RED_1") (pintype "bidirectional"))
      (node (ref "LED_46") (pin "1") (pinfunction "RED_1") (pintype "bidirectional"))
      (node (ref "LED_54") (pin "1") (pinfunction "RED_1") (pintype "bidirectional"))
      (node (ref "LED_6") (pin "1") (pinfunction "RED_1") (pintype "bidirectional"))
      (node (ref "LED_62") (pin "1") (pinfunction "RED_1") (pintype "bidirectional"))
      (node (ref "R20") (pin "6") (pinfunction "2_6") (pintype "passive"))
    )
    (net (code "94") (name "RCOL6") (class "Default")
      (node (ref "LED_15") (pin "1") (pinfunction "RED_1") (pintype "bidirectional"))
      (node (ref "LED_23") (pin "1") (pinfunction "RED_1") (pintype "bidirectional"))
      (node (ref "LED_31") (pin "1") (pinfunction "RED_1") (pintype "bidirectional"))
      (node (ref "LED_39") (pin "1") (pinfunction "RED_1") (pintype "bidirectional"))
      (node (ref "LED_47") (pin "1") (pinfunction "RED_1") (pintype "bidirectional"))
      (node (ref "LED_55") (pin "1") (pinfunction "RED_1") (pintype "bidirectional"))
      (node (ref "LED_63") (pin "1") (pinfunction "RED_1") (pintype "bidirectional"))
      (node (ref "LED_7") (pin "1") (pinfunction "RED_1") (pintype "bidirectional"))
      (node (ref "R20") (pin "7") (pinfunction "2_7") (pintype "passive"))
    )
    (net (code "95") (name "RCOL7") (class "Default")
      (node (ref "LED_16") (pin "1") (pinfunction "RED_1") (pintype "bidirectional"))
      (node (ref "LED_24") (pin "1") (pinfunction "RED_1") (pintype "bidirectional"))
      (node (ref "LED_32") (pin "1") (pinfunction "RED_1") (pintype "bidirectional"))
      (node (ref "LED_40") (pin "1") (pinfunction "RED_1") (pintype "bidirectional"))
      (node (ref "LED_48") (pin "1") (pinfunction "RED_1") (pintype "bidirectional"))
      (node (ref "LED_56") (pin "1") (pinfunction "RED_1") (pintype "bidirectional"))
      (node (ref "LED_64") (pin "1") (pinfunction "RED_1") (pintype "bidirectional"))
      (node (ref "LED_8") (pin "1") (pinfunction "RED_1") (pintype "bidirectional"))
      (node (ref "R20") (pin "8") (pinfunction "2_8") (pintype "passive"))
    )
    (net (code "96") (name "USB_5V") (class "Default")
      (node (ref "C17") (pin "1") (pinfunction "1_1") (pintype "passive"))
      (node (ref "CON1") (pin "PIN$1") (pinfunction "VCC_PIN$1") (pintype "bidirectional"))
      (node (ref "D3") (pin "A") (pinfunction "A_A") (pintype "passive"))
      (node (ref "U$8") (pin "4") (pinfunction "VCC_4") (pintype "bidirectional"))
      (node (ref "Z3") (pin "2") (pinfunction "2_2") (pintype "passive"))
    )
    (net (code "97") (name "USB_D+") (class "Default")
      (node (ref "R8") (pin "2") (pinfunction "2_2") (pintype "passive"))
      (node (ref "U1") (pin "3") (pinfunction "USB0_DP_3") (pintype "bidirectional"))
    )
    (net (code "98") (name "USB_D-") (class "Default")
      (node (ref "R7") (pin "2") (pinfunction "2_2") (pintype "passive"))
      (node (ref "U1") (pin "4") (pinfunction "USB0_DM_4") (pintype "bidirectional"))
    )
    (net (code "99") (name "VBAT") (class "Default")
      (node (ref "BAT") (pin "+") (pinfunction "+_+") (pintype "bidirectional"))
      (node (ref "C12") (pin "1") (pinfunction "1_1") (pintype "passive"))
      (node (ref "L1") (pin "P$1") (pinfunction "1_P$1") (pintype "passive"))
      (node (ref "TP8") (pin "TP") (pinfunction "TP_TP") (pintype "input"))
      (node (ref "U$8") (pin "3") (pinfunction "BAT_3") (pintype "bidirectional"))
    )
    (net (code "100") (name "unconnected-(CON1-ID-PadPIN$4)") (class "Default")
      (node (ref "CON1") (pin "PIN$4") (pinfunction "ID_PIN$4") (pintype "bidirectional"))
    )
    (net (code "101") (name "unconnected-(U1-EXTAL32-Pad10)") (class "Default")
      (node (ref "U1") (pin "10") (pinfunction "EXTAL32_10") (pintype "bidirectional"))
    )
    (net (code "102") (name "unconnected-(U1-PTC2-Pad23)") (class "Default")
      (node (ref "U1") (pin "23") (pinfunction "PTC2_23") (pintype "bidirectional"))
    )
    (net (code "103") (name "unconnected-(U1-PTC7-Pad28)") (class "Default")
      (node (ref "U1") (pin "28") (pinfunction "PTC7_28") (pintype "bidirectional"))
    )
    (net (code "104") (name "unconnected-(U1-XTAL32-Pad9)") (class "Default")
      (node (ref "U1") (pin "9") (pinfunction "XTAL32_9") (pintype "bidirectional"))
    )
    (net (code "105") (name "unconnected-(U4-DOUT-Pad22)") (class "Default")
      (node (ref "U4") (pin "22") (pinfunction "DOUT_22") (pintype "bidirectional"))
    )
    (net (code "106") (name "unconnected-(U4-OUT8-Pad13)") (class "Default")
      (node (ref "U4") (pin "13") (pinfunction "OUT8_13") (pintype "bidirectional"))
    )
    (net (code "107") (name "unconnected-(U4-OUT9-Pad14)") (class "Default")
      (node (ref "U4") (pin "14") (pinfunction "OUT9_14") (pintype "bidirectional"))
    )
    (net (code "108") (name "unconnected-(U4-OUT10-Pad15)") (class "Default")
      (node (ref "U4") (pin "15") (pinfunction "OUT10_15") (pintype "bidirectional"))
    )
    (net (code "109") (name "unconnected-(U4-OUT11-Pad16)") (class "Default")
      (node (ref "U4") (pin "16") (pinfunction "OUT11_16") (pintype "bidirectional"))
    )
    (net (code "110") (name "unconnected-(U4-OUT12-Pad17)") (class "Default")
      (node (ref "U4") (pin "17") (pinfunction "OUT12_17") (pintype "bidirectional"))
    )
    (net (code "111") (name "unconnected-(U4-OUT13-Pad18)") (class "Default")
      (node (ref "U4") (pin "18") (pinfunction "OUT13_18") (pintype "bidirectional"))
    )
    (net (code "112") (name "unconnected-(U4-OUT14-Pad19)") (class "Default")
      (node (ref "U4") (pin "19") (pinfunction "OUT14_19") (pintype "bidirectional"))
    )
    (net (code "113") (name "unconnected-(U4-OUT15-Pad20)") (class "Default")
      (node (ref "U4") (pin "20") (pinfunction "OUT15_20") (pintype "bidirectional"))
    )
    (net (code "114") (name "unconnected-(U8-INT2-PadP$5)") (class "Default")
      (node (ref "U8") (pin "P$5") (pinfunction "INT2_P$5") (pintype "bidirectional"))
    )
  )
)
